# sound.net
KiCad netlist of a schematic drawn in EAGLE
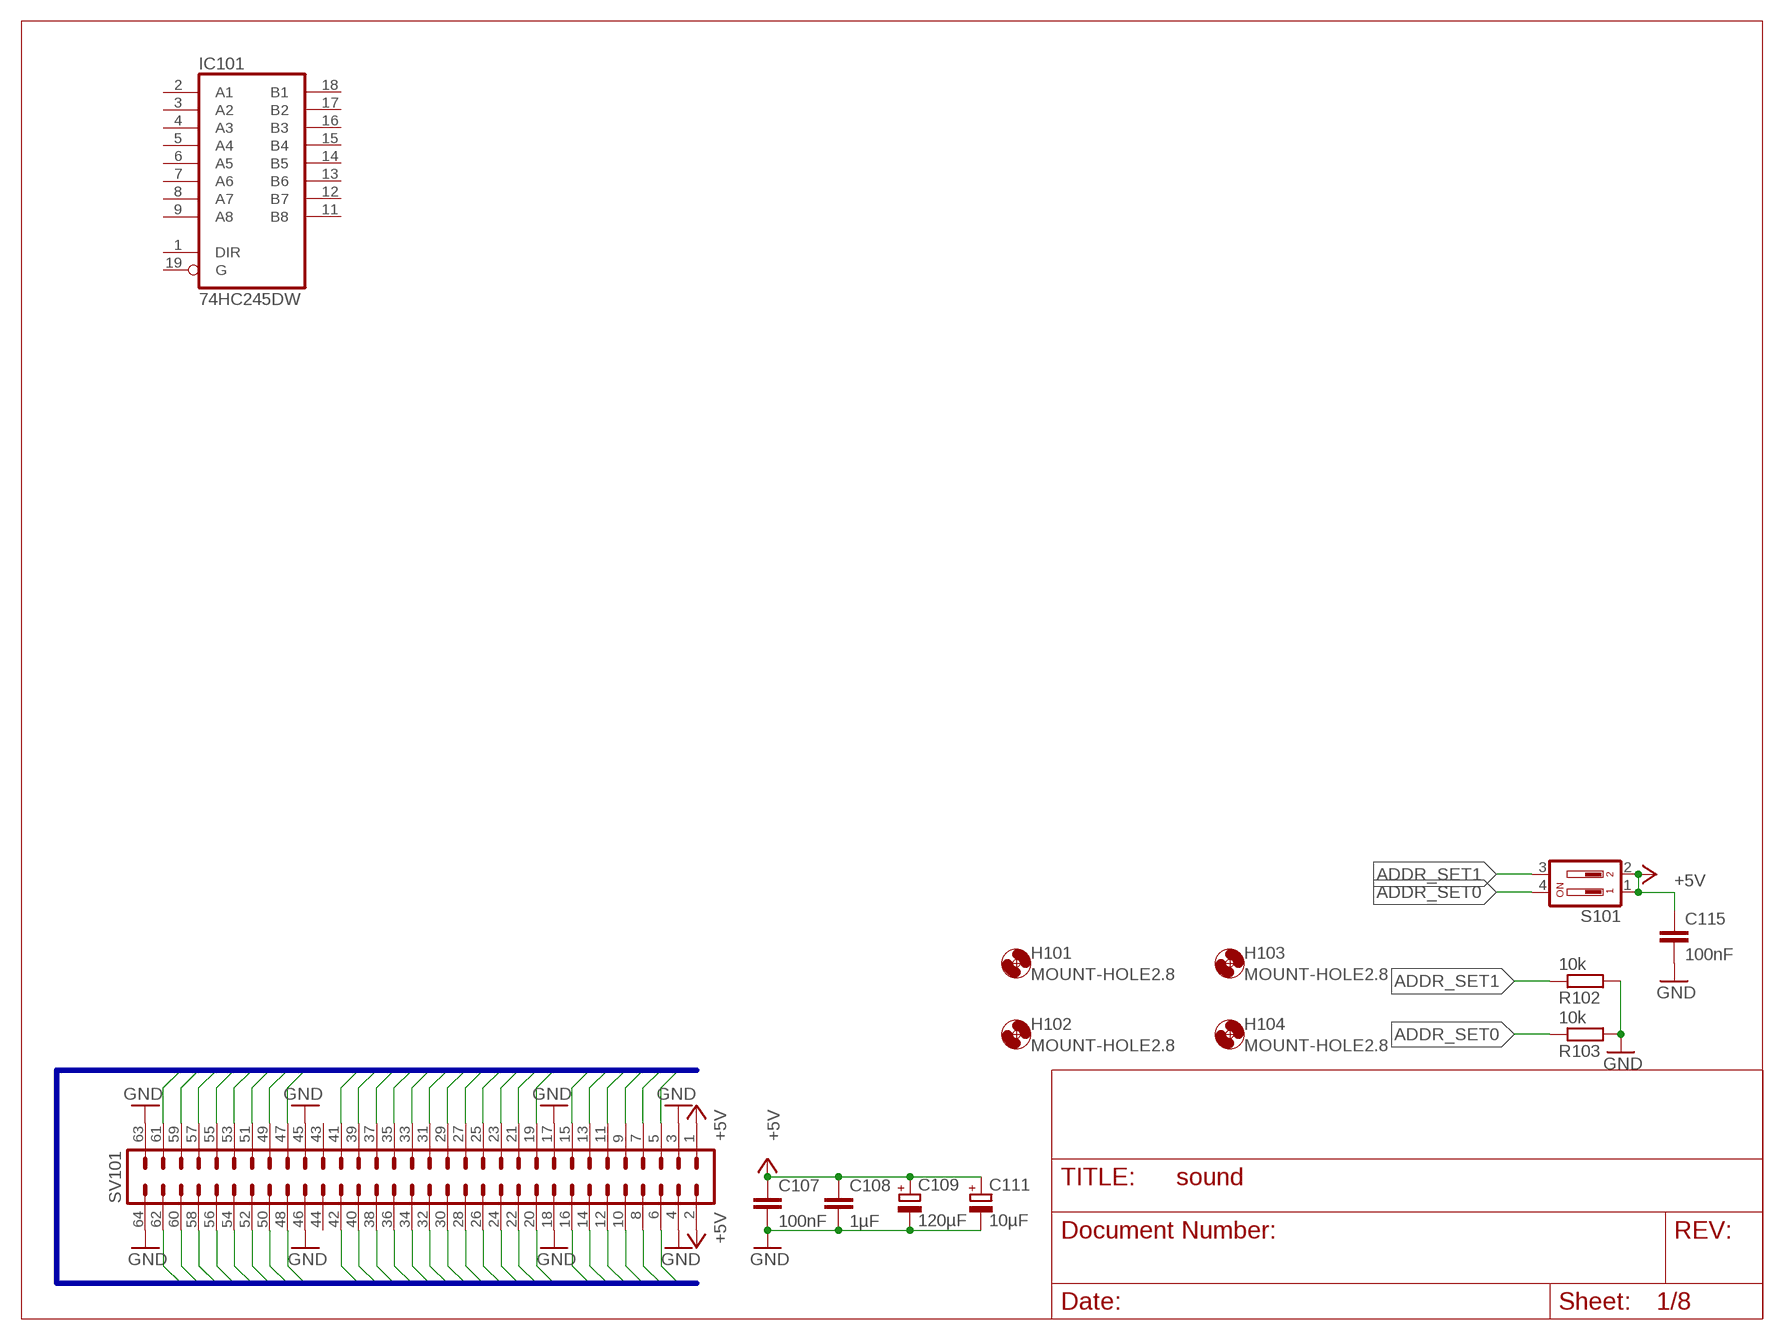
[diagram p0: schematic, sheet 1]
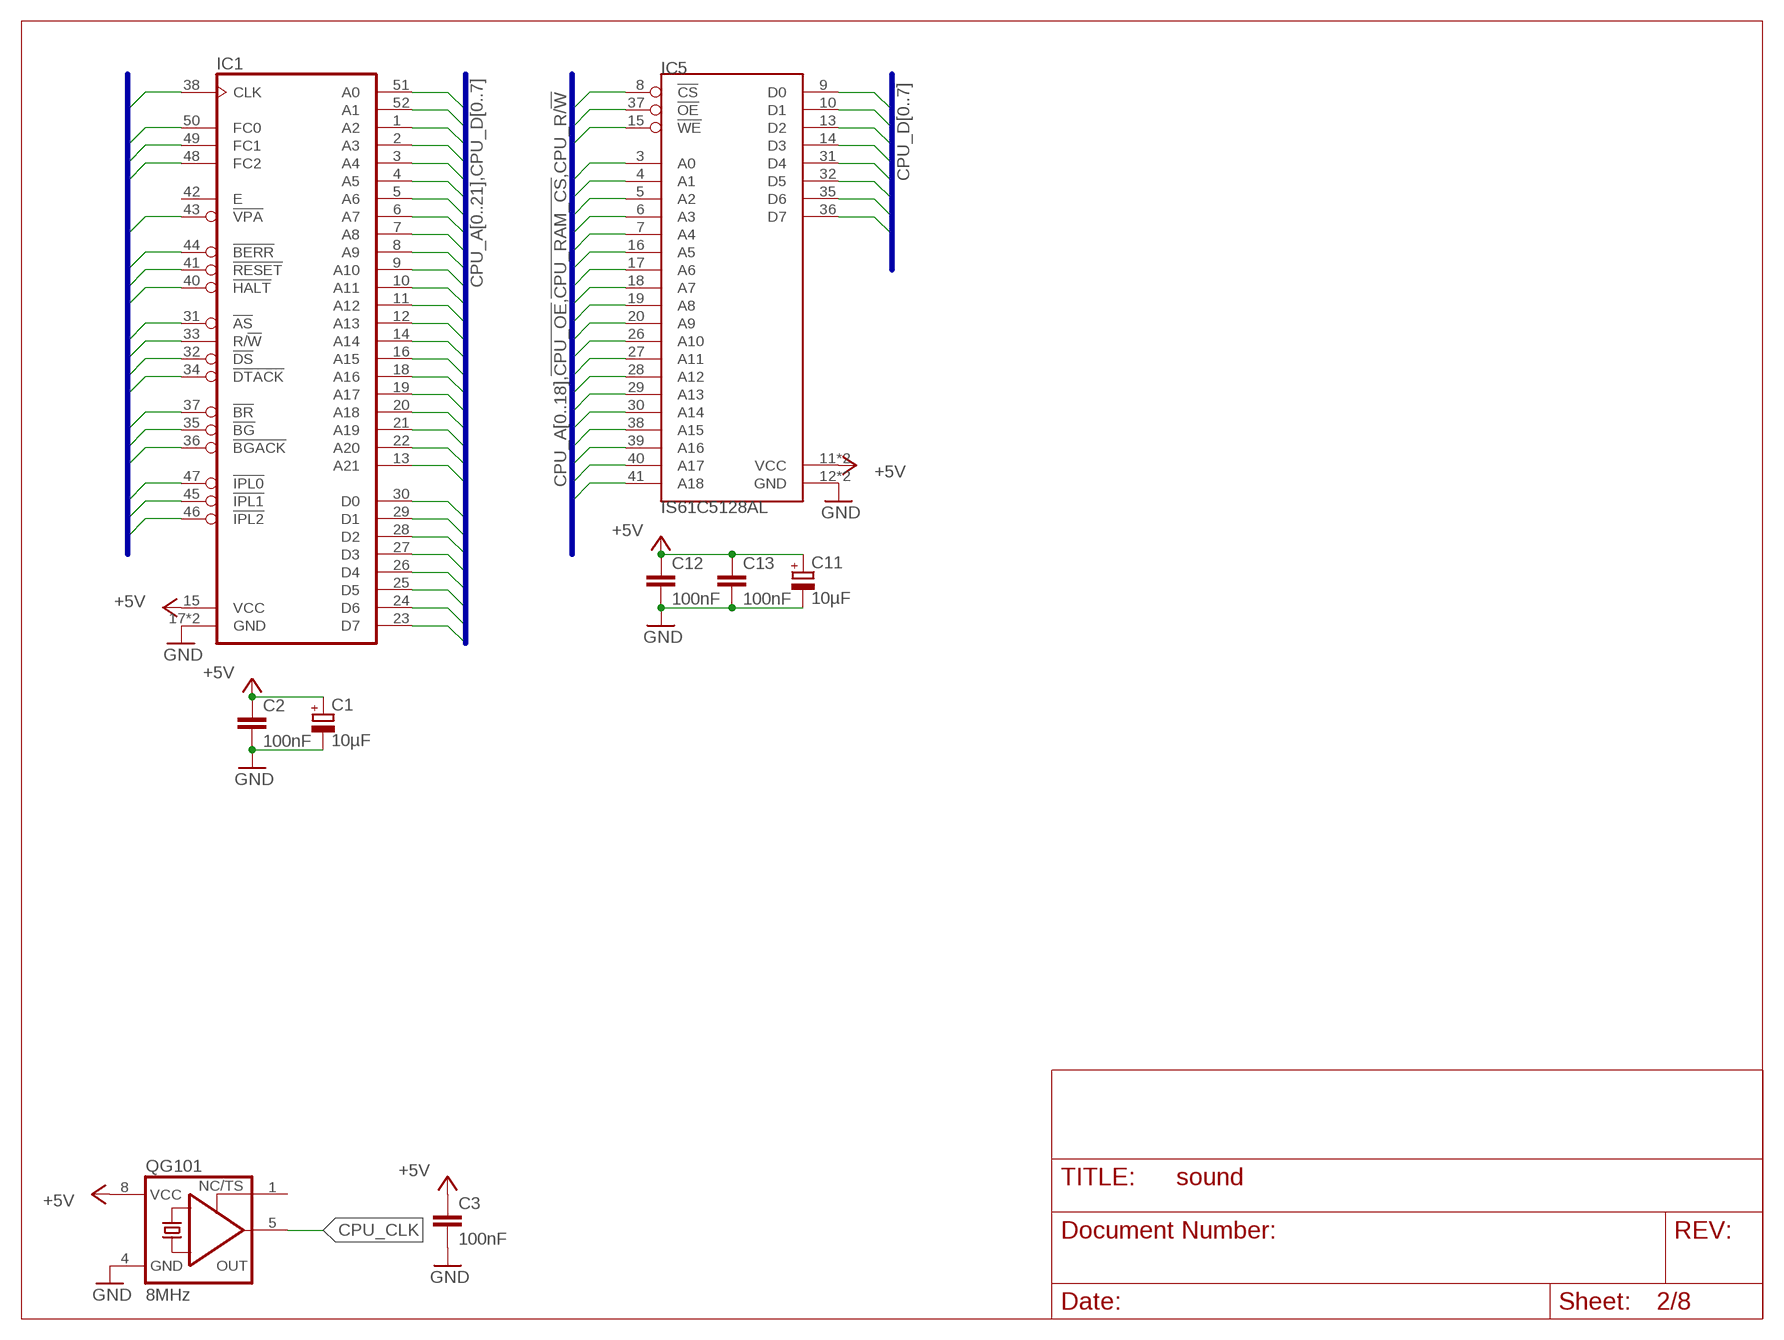
[diagram p1: schematic, sheet 2]
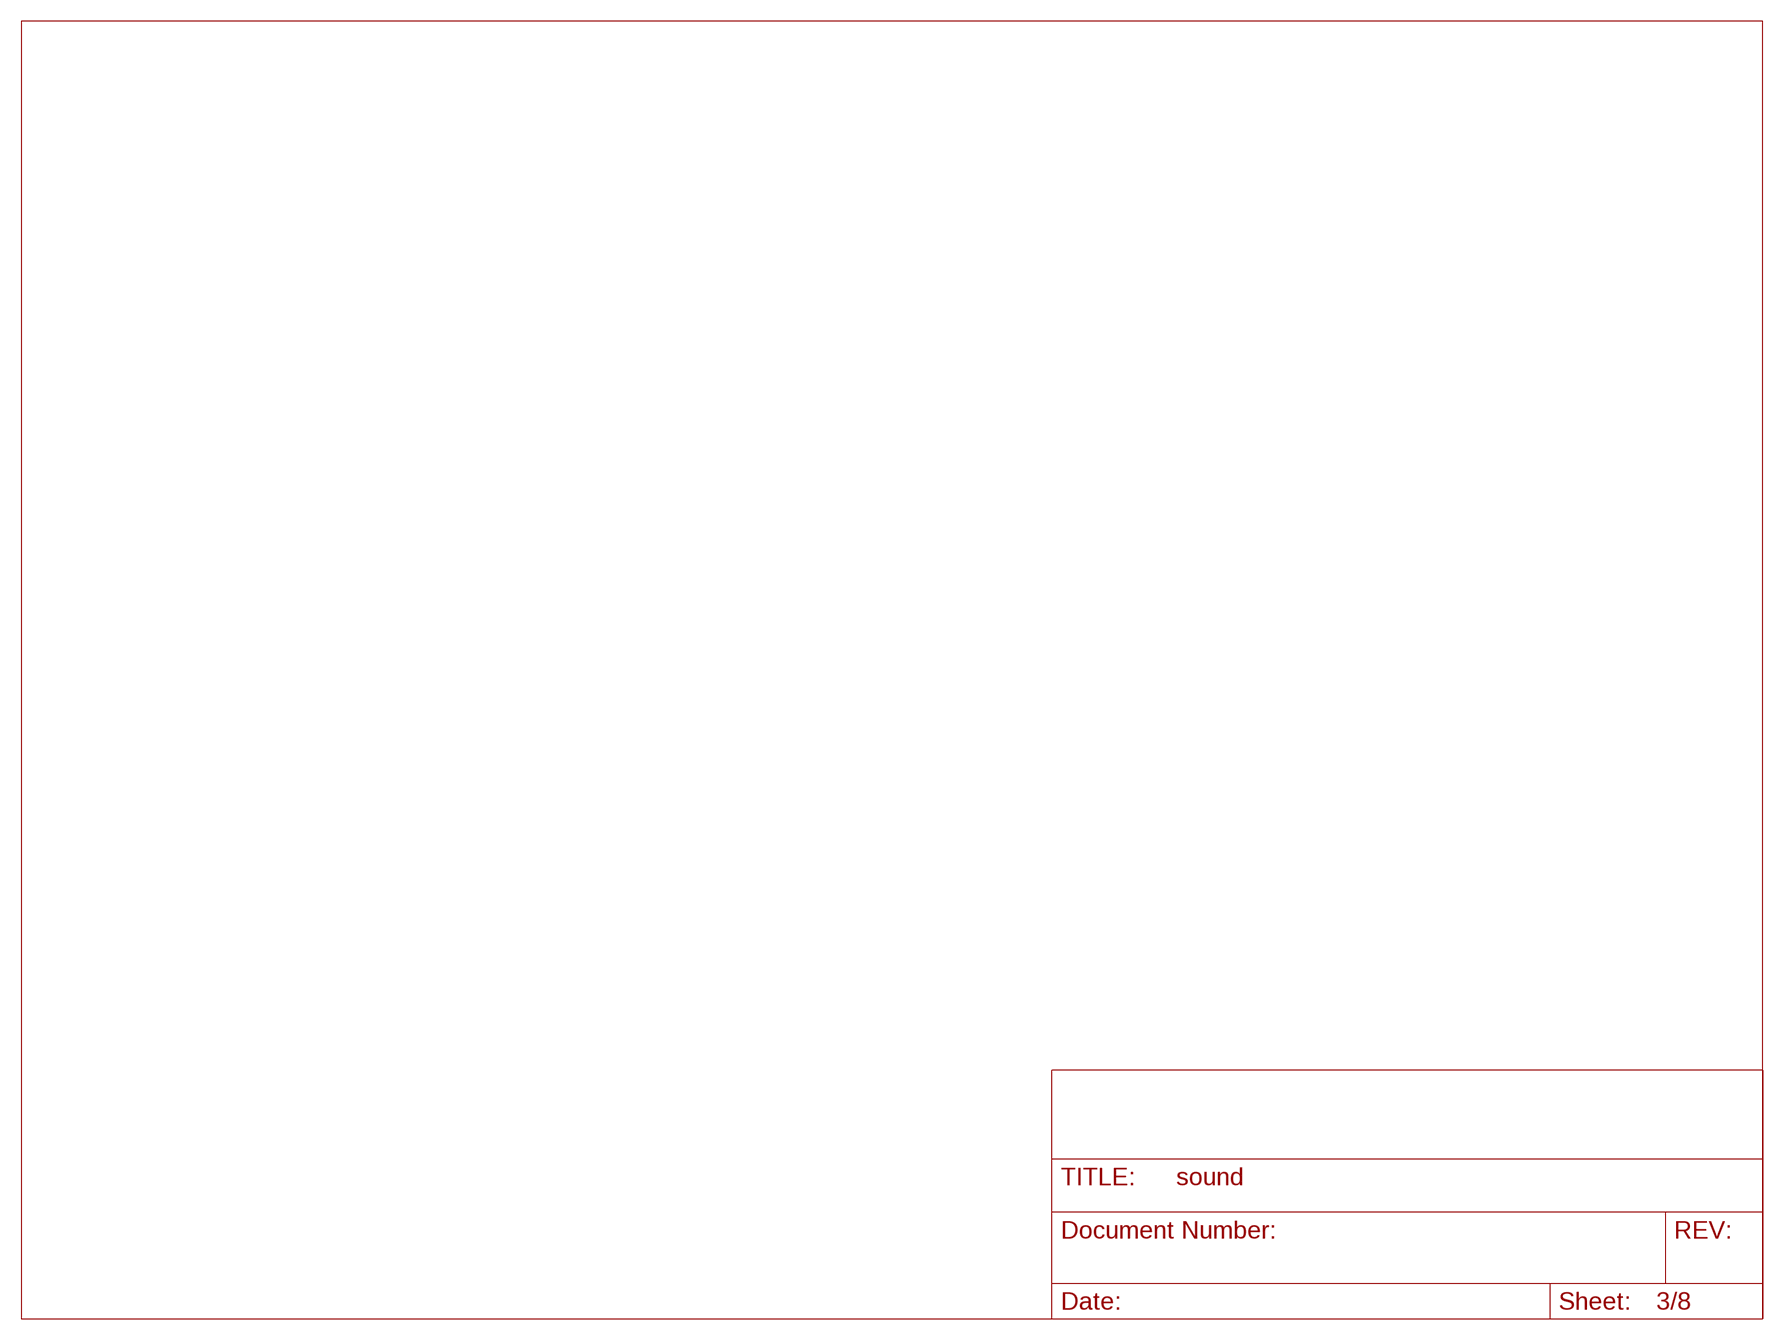
[diagram p2: schematic, sheet 3]
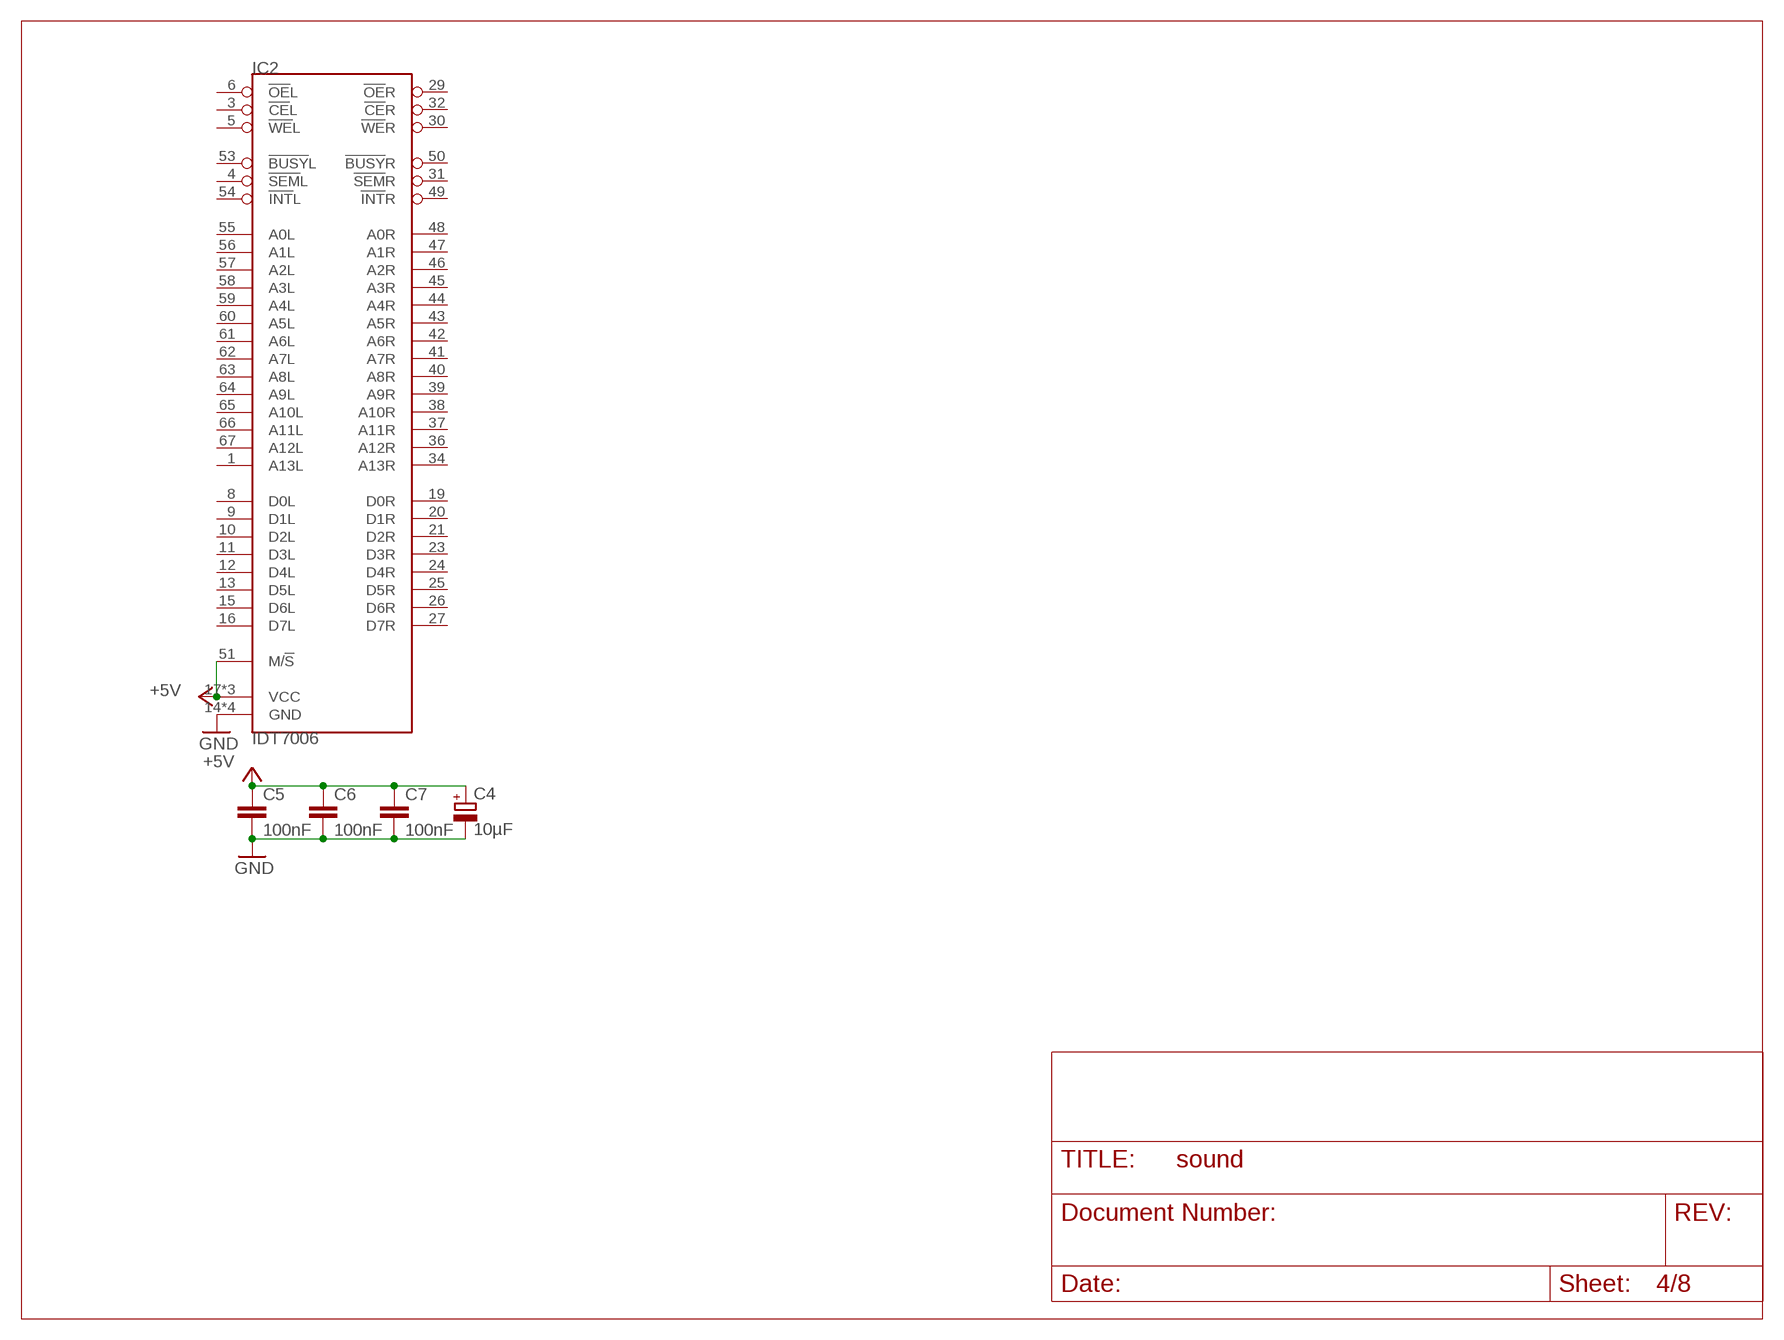
[diagram p3: schematic, sheet 4]
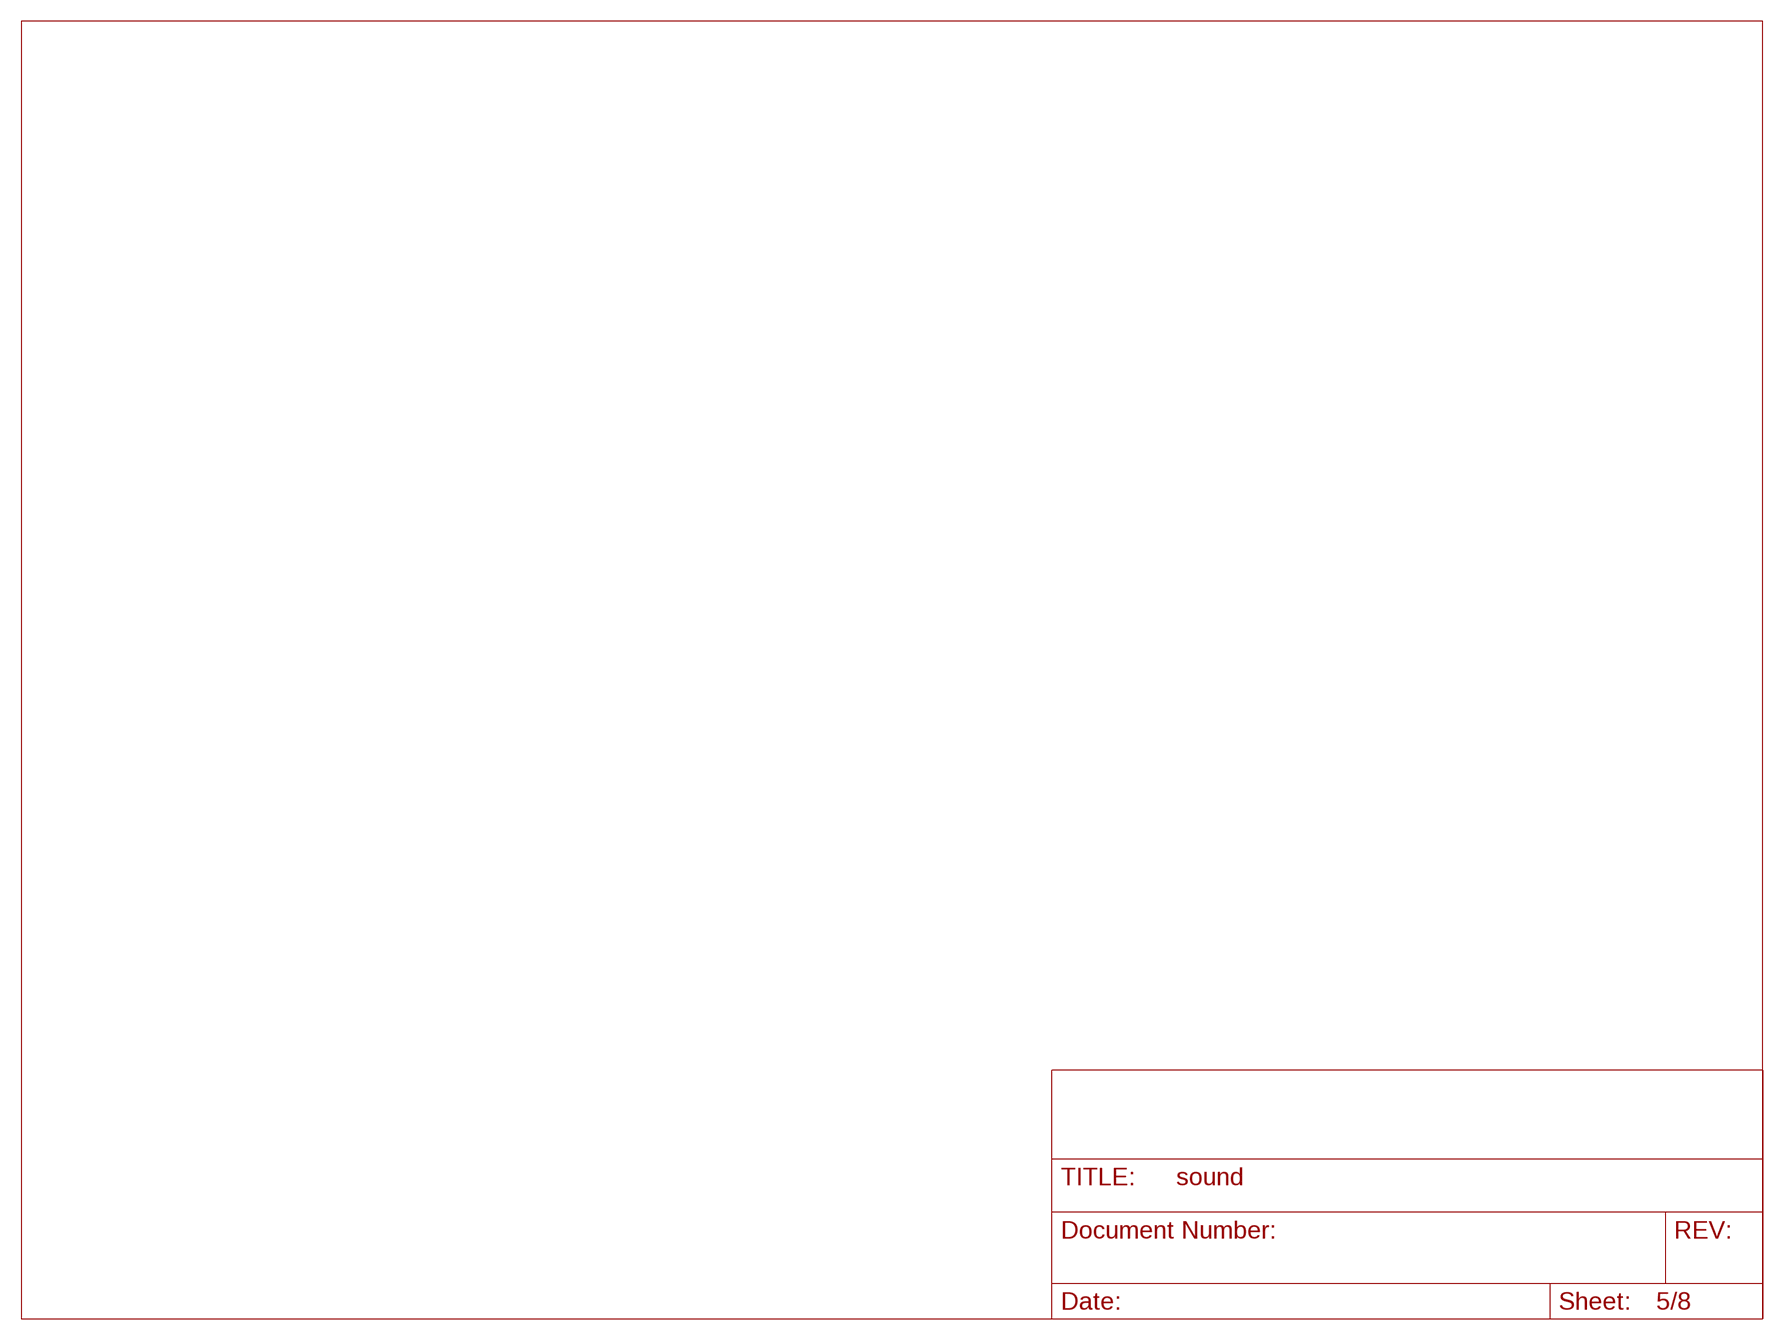
[diagram p4: schematic, sheet 5]
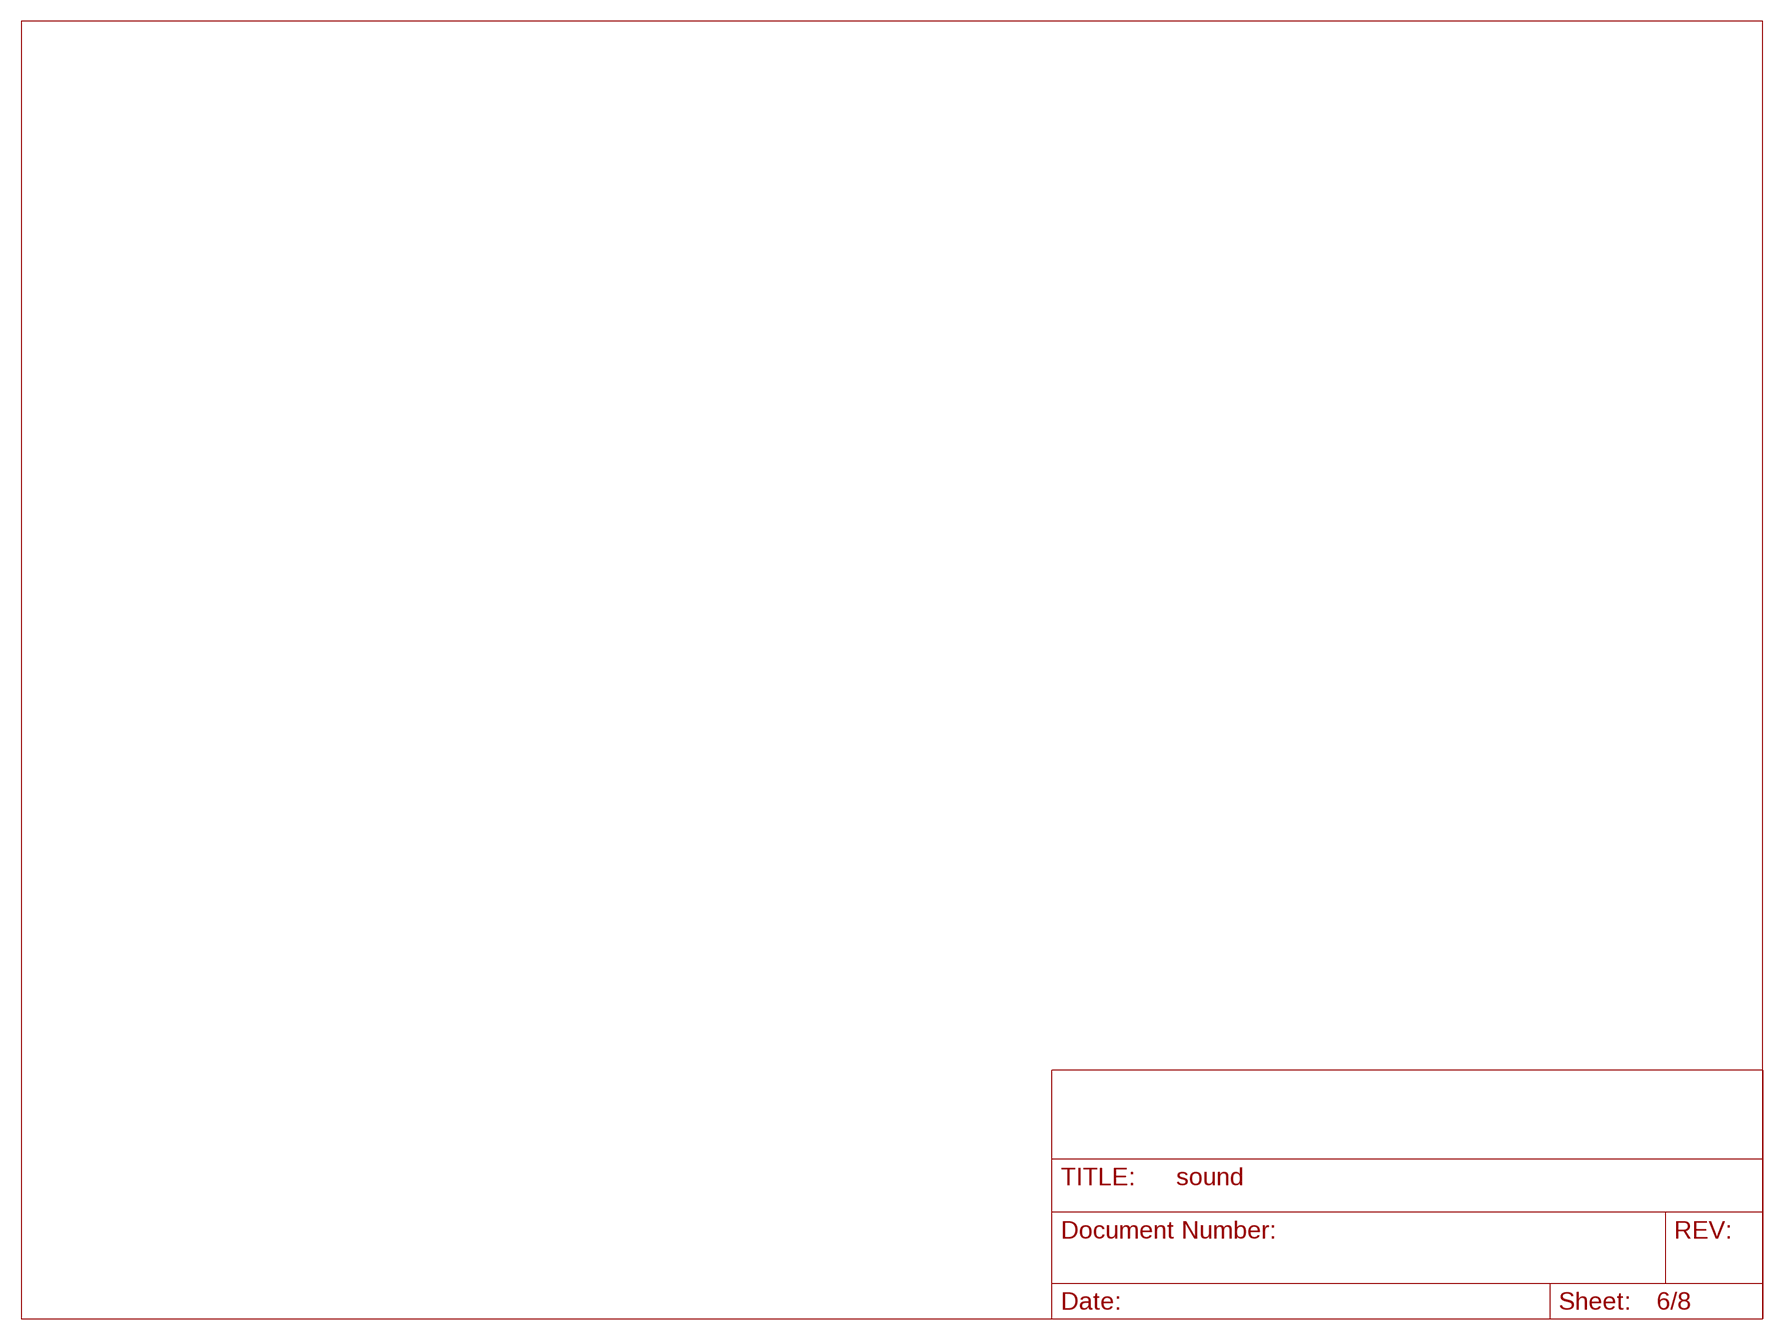
[diagram p5: schematic, sheet 6]
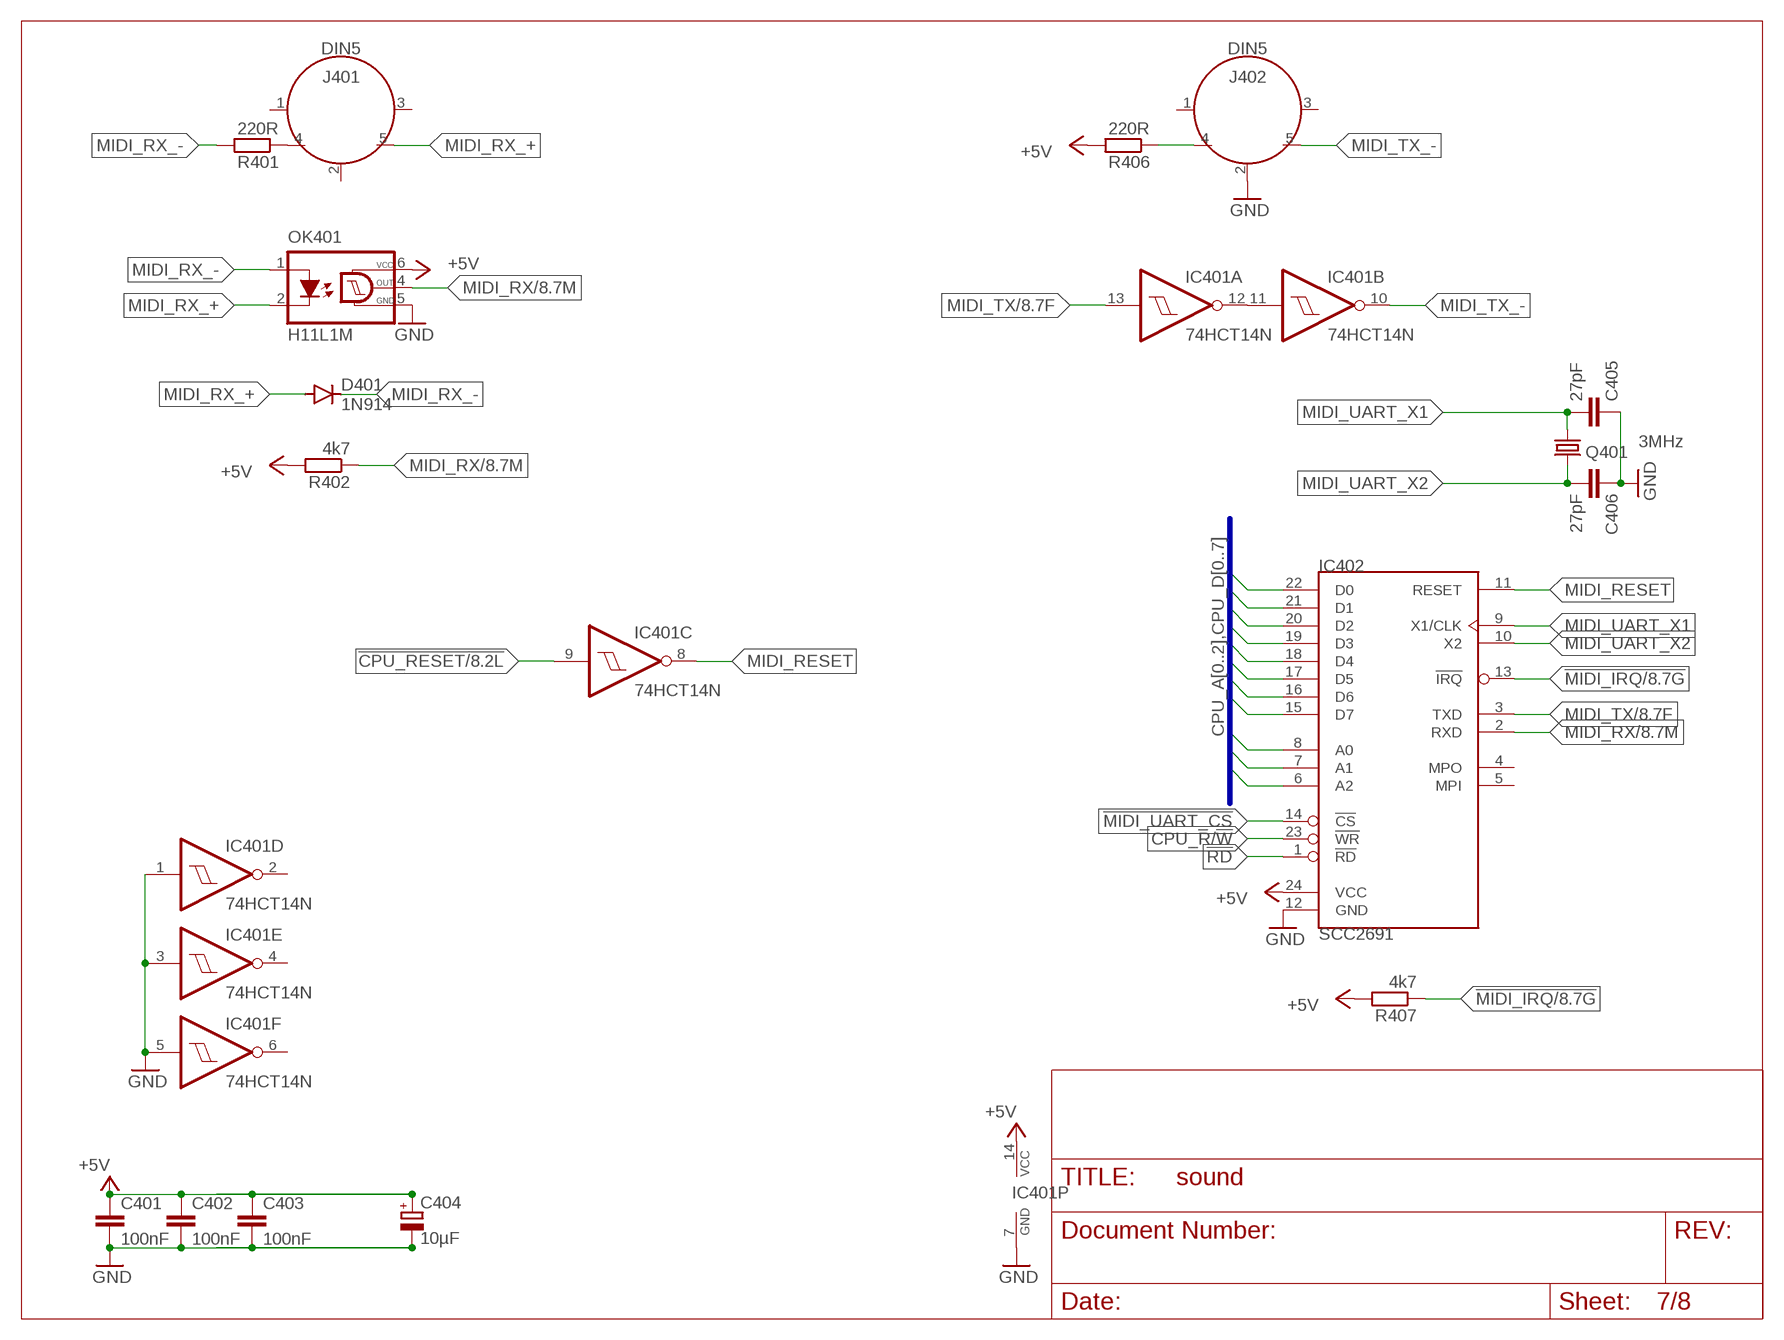
[diagram p6: schematic, sheet 7]
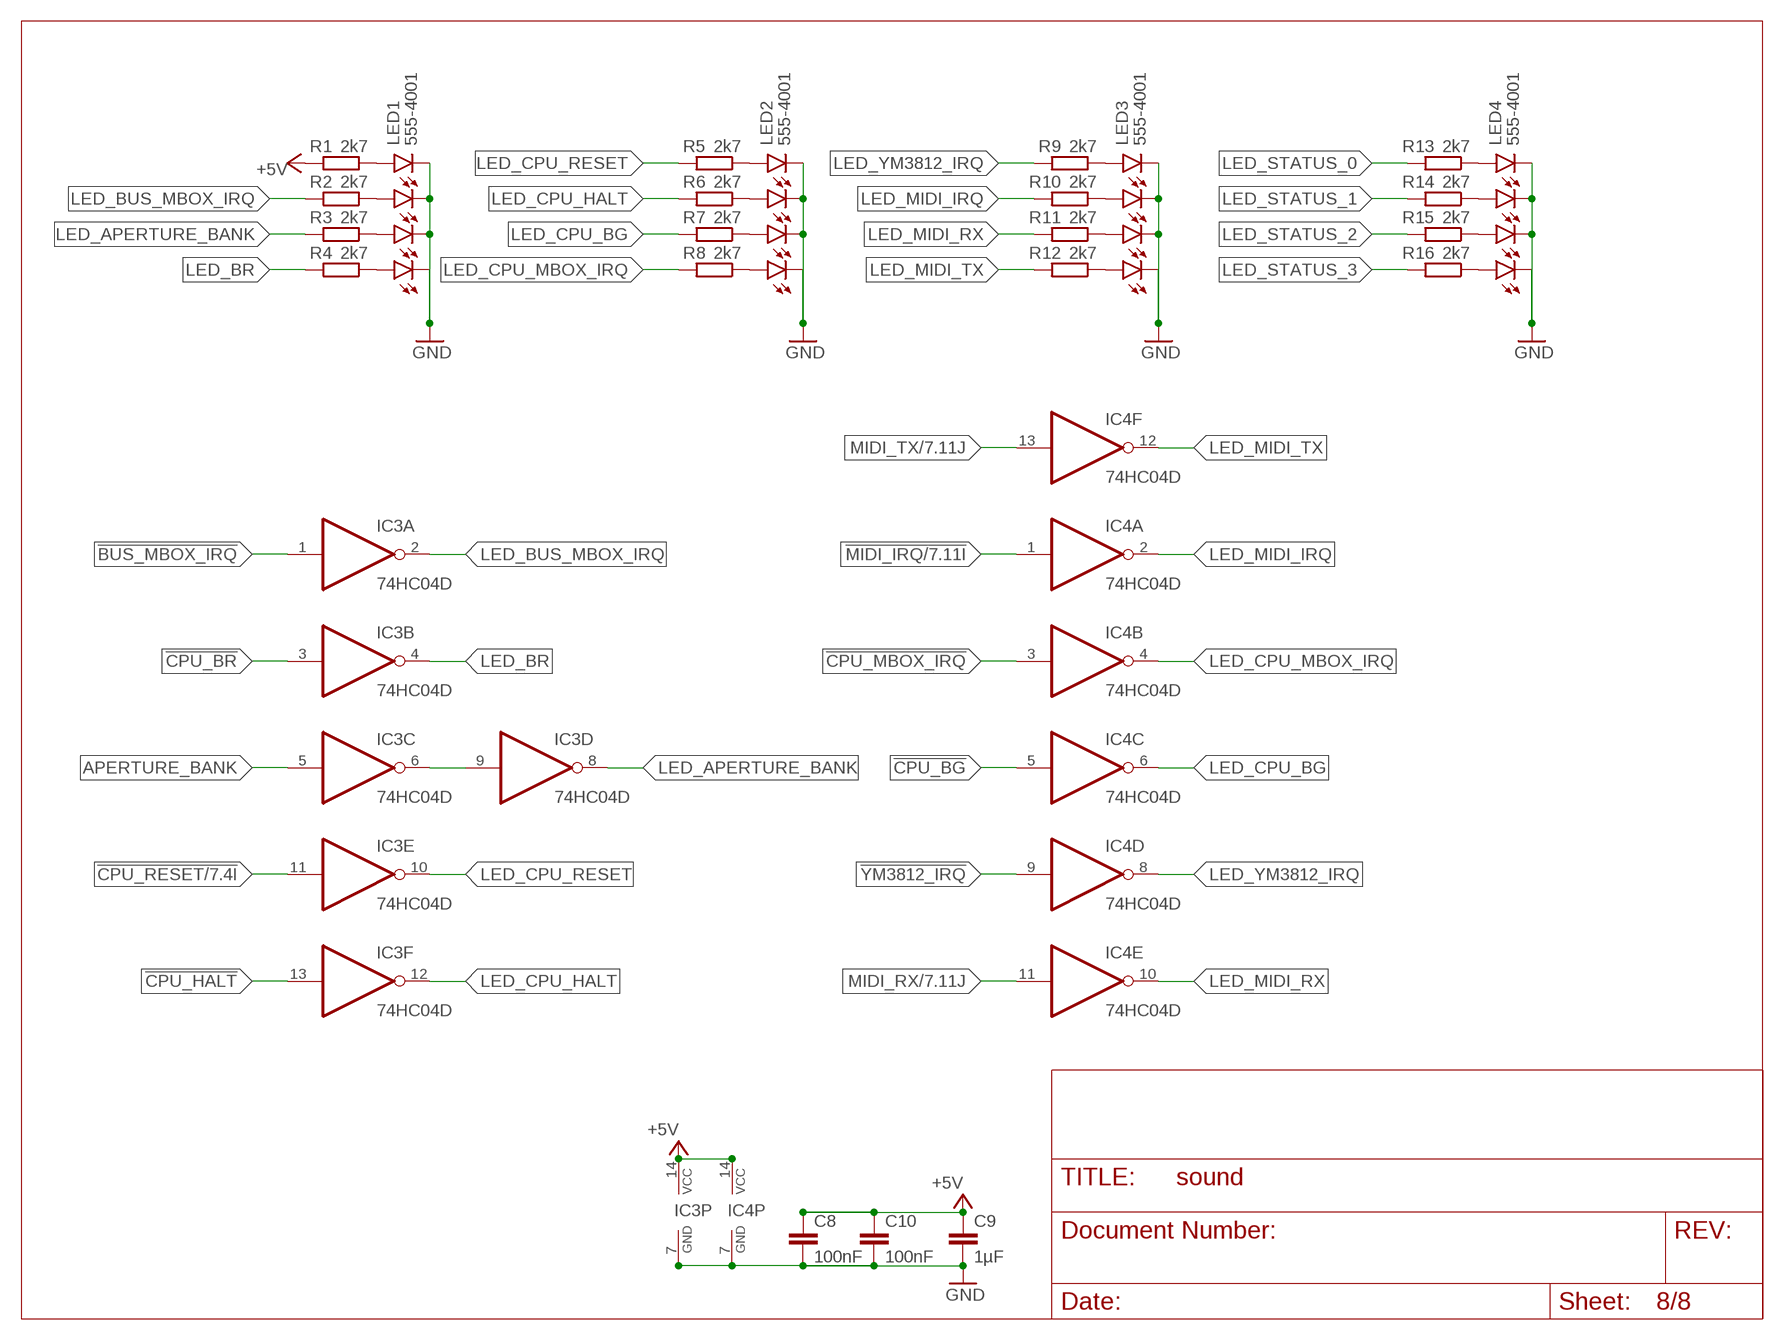
[diagram p7: schematic, sheet 8]

(export (version "E")
  (design (tool "Eeschema 10.0.6"))
  (components
    (comp (ref "C4")
      (value "10µF")
      (footprint "eagle-import:SMC_B")
      (libsource (lib "eagle-import") (part "CPOL-EUSMCB"))
    )
    (comp (ref "C5")
      (value "100nF")
      (footprint "eagle-import:C0805")
      (libsource (lib "eagle-import") (part "C-EUC0805"))
    )
    (comp (ref "C6")
      (value "100nF")
      (footprint "eagle-import:C0805")
      (libsource (lib "eagle-import") (part "C-EUC0805"))
    )
    (comp (ref "C7")
      (value "100nF")
      (footprint "eagle-import:C0805")
      (libsource (lib "eagle-import") (part "C-EUC0805"))
    )
    (comp (ref "IC2")
      (value "IDT7006")
      (footprint "eagle-import:PLCC68-S")
      (libsource (lib "eagle-import") (part "IDT7006PLCC68-S"))
    )
    (comp (ref "C107")
      (value "100nF")
      (footprint "eagle-import:C0805")
      (libsource (lib "eagle-import") (part "C-EUC0805"))
    )
    (comp (ref "C108")
      (value "1µF")
      (footprint "eagle-import:C0805")
      (libsource (lib "eagle-import") (part "C-EUC0805"))
    )
    (comp (ref "C109")
      (value "120µF")
      (footprint "eagle-import:E2,5-7")
      (libsource (lib "eagle-import") (part "CPOL-EUE2.5-7"))
    )
    (comp (ref "C111")
      (value "10µF")
      (footprint "eagle-import:SMC_B")
      (libsource (lib "eagle-import") (part "CPOL-EUSMCB"))
    )
    (comp (ref "C115")
      (value "100nF")
      (footprint "eagle-import:C0805")
      (libsource (lib "eagle-import") (part "C-EUC0805"))
    )
    (comp (ref "H101")
      (value "MOUNT-HOLE2.8")
      (footprint "eagle-import:2,8")
      (libsource (lib "eagle-import") (part "MOUNT-HOLE2.8"))
    )
    (comp (ref "H102")
      (value "MOUNT-HOLE2.8")
      (footprint "eagle-import:2,8")
      (libsource (lib "eagle-import") (part "MOUNT-HOLE2.8"))
    )
    (comp (ref "H103")
      (value "MOUNT-HOLE2.8")
      (footprint "eagle-import:2,8")
      (libsource (lib "eagle-import") (part "MOUNT-HOLE2.8"))
    )
    (comp (ref "H104")
      (value "MOUNT-HOLE2.8")
      (footprint "eagle-import:2,8")
      (libsource (lib "eagle-import") (part "MOUNT-HOLE2.8"))
    )
    (comp (ref "IC101")
      (value "74HC245DW")
      (footprint "eagle-import:SO20W")
      (libsource (lib "eagle-import") (part "74245DWHC"))
    )
    (comp (ref "R102")
      (value "10k")
      (footprint "eagle-import:R2012")
      (libsource (lib "eagle-import") (part "R-EU_R2012"))
    )
    (comp (ref "R103")
      (value "10k")
      (footprint "eagle-import:R2012")
      (libsource (lib "eagle-import") (part "R-EU_R2012"))
    )
    (comp (ref "S101")
      (value "DP02")
      (footprint "eagle-import:DP-02")
      (fields (field (name "MPN") "MCDP02"))
      (libsource (lib "eagle-import") (part "DP02"))
    )
    (comp (ref "SV101")
      (value "ML64L")
      (footprint "eagle-import:ML64L")
      (libsource (lib "eagle-import") (part "ML64L"))
    )
    (comp (ref "C401")
      (value "100nF")
      (footprint "eagle-import:C0805")
      (libsource (lib "eagle-import") (part "C-EUC0805"))
    )
    (comp (ref "C402")
      (value "100nF")
      (footprint "eagle-import:C0805")
      (libsource (lib "eagle-import") (part "C-EUC0805"))
    )
    (comp (ref "C403")
      (value "100nF")
      (footprint "eagle-import:C0805")
      (libsource (lib "eagle-import") (part "C-EUC0805"))
    )
    (comp (ref "C404")
      (value "10µF")
      (footprint "eagle-import:SMC_B")
      (libsource (lib "eagle-import") (part "CPOL-EUSMCB"))
    )
    (comp (ref "C405")
      (value "27pF")
      (footprint "eagle-import:C0805")
      (libsource (lib "eagle-import") (part "C-EUC0805"))
    )
    (comp (ref "C406")
      (value "27pF")
      (footprint "eagle-import:C0805")
      (libsource (lib "eagle-import") (part "C-EUC0805"))
    )
    (comp (ref "D401")
      (value "1N914")
      (footprint "eagle-import:DO35-10")
      (libsource (lib "eagle-import") (part "1N4148DO35-10"))
    )
    (comp (ref "IC401")
      (value "74HCT14N")
      (footprint "eagle-import:DIL14")
      (fields (field (name "MOUSER") "595-SN74HCT14N") (field (name "MOUSER_SOCKET") "575-1104731441001000"))
      (libsource (lib "eagle-import") (part "7414NHCT"))
    )
    (comp (ref "IC402")
      (value "SCC2691")
      (footprint "eagle-import:DIL24S")
      (libsource (lib "eagle-import") (part "SCC2691"))
    )
    (comp (ref "J401")
      (value "DIN5")
      (footprint "eagle-import:DIN5-RA-PTH")
      (libsource (lib "eagle-import") (part "DIN5"))
    )
    (comp (ref "J402")
      (value "DIN5")
      (footprint "eagle-import:DIN5-RA-PTH")
      (libsource (lib "eagle-import") (part "DIN5"))
    )
    (comp (ref "OK401")
      (value "H11L1M")
      (footprint "eagle-import:DIL06")
      (fields (field (name "MF") "FAIRCHILD SEMICONDUCTOR") (field (name "MPN") "H11L1-M"))
      (libsource (lib "eagle-import") (part "H11LM1"))
    )
    (comp (ref "Q401")
      (value "3MHz")
      (footprint "eagle-import:HC49_S")
      (libsource (lib "eagle-import") (part "CRYSTALHC49S"))
    )
    (comp (ref "R401")
      (value "220R")
      (footprint "eagle-import:R2012")
      (libsource (lib "eagle-import") (part "R-EU_R2012"))
    )
    (comp (ref "R402")
      (value "4k7")
      (footprint "eagle-import:R2012")
      (libsource (lib "eagle-import") (part "R-EU_R2012"))
    )
    (comp (ref "R406")
      (value "220R")
      (footprint "eagle-import:R2012")
      (libsource (lib "eagle-import") (part "R-EU_R2012"))
    )
    (comp (ref "R407")
      (value "4k7")
      (footprint "eagle-import:R2012")
      (libsource (lib "eagle-import") (part "R-EU_R2012"))
    )
    (comp (ref "C1")
      (value "10µF")
      (footprint "eagle-import:SMC_B")
      (libsource (lib "eagle-import") (part "CPOL-EUSMCB"))
    )
    (comp (ref "C2")
      (value "100nF")
      (footprint "eagle-import:C0805")
      (libsource (lib "eagle-import") (part "C-EUC0805"))
    )
    (comp (ref "C3")
      (value "100nF")
      (footprint "eagle-import:C0805")
      (libsource (lib "eagle-import") (part "C-EUC0805"))
    )
    (comp (ref "C11")
      (value "10µF")
      (footprint "eagle-import:SMC_B")
      (libsource (lib "eagle-import") (part "CPOL-EUSMCB"))
    )
    (comp (ref "C12")
      (value "100nF")
      (footprint "eagle-import:C0805")
      (libsource (lib "eagle-import") (part "C-EUC0805"))
    )
    (comp (ref "C13")
      (value "100nF")
      (footprint "eagle-import:C0805")
      (libsource (lib "eagle-import") (part "C-EUC0805"))
    )
    (comp (ref "IC1")
      (value "MC68008-PLCCPLCC52-SOCKET")
      (footprint "eagle-import:PLCC52-S")
      (libsource (lib "eagle-import") (part "MC68008-PLCCPLCC52-SOCKET"))
    )
    (comp (ref "IC5")
      (value "IS61C5128AL")
      (footprint "eagle-import:TSOP44-II")
      (libsource (lib "eagle-import") (part "IS61C5128AL"))
    )
    (comp (ref "QG101")
      (value "8MHz")
      (footprint "eagle-import:DIL08S")
      (libsource (lib "eagle-import") (part "XO-8"))
    )
    (comp (ref "C8")
      (value "100nF")
      (footprint "eagle-import:C0805")
      (libsource (lib "eagle-import") (part "C-EUC0805"))
    )
    (comp (ref "C9")
      (value "1µF")
      (footprint "eagle-import:C0805")
      (libsource (lib "eagle-import") (part "C-EUC0805"))
    )
    (comp (ref "C10")
      (value "100nF")
      (footprint "eagle-import:C0805")
      (libsource (lib "eagle-import") (part "C-EUC0805"))
    )
    (comp (ref "IC3")
      (value "74HC04D")
      (footprint "eagle-import:SO14")
      (libsource (lib "eagle-import") (part "7404DHC"))
    )
    (comp (ref "IC4")
      (value "74HC04D")
      (footprint "eagle-import:SO14")
      (libsource (lib "eagle-import") (part "7404DHC"))
    )
    (comp (ref "LED1")
      (value "555-4001")
      (footprint "eagle-import:555-4001")
      (libsource (lib "eagle-import") (part "555-4001"))
    )
    (comp (ref "LED2")
      (value "555-4001")
      (footprint "eagle-import:555-4001")
      (libsource (lib "eagle-import") (part "555-4001"))
    )
    (comp (ref "LED3")
      (value "555-4001")
      (footprint "eagle-import:555-4001")
      (libsource (lib "eagle-import") (part "555-4001"))
    )
    (comp (ref "LED4")
      (value "555-4001")
      (footprint "eagle-import:555-4001")
      (libsource (lib "eagle-import") (part "555-4001"))
    )
    (comp (ref "R1")
      (value "2k7")
      (footprint "eagle-import:R2012")
      (libsource (lib "eagle-import") (part "R-EU_R2012"))
    )
    (comp (ref "R2")
      (value "2k7")
      (footprint "eagle-import:R2012")
      (libsource (lib "eagle-import") (part "R-EU_R2012"))
    )
    (comp (ref "R3")
      (value "2k7")
      (footprint "eagle-import:R2012")
      (libsource (lib "eagle-import") (part "R-EU_R2012"))
    )
    (comp (ref "R4")
      (value "2k7")
      (footprint "eagle-import:R2012")
      (libsource (lib "eagle-import") (part "R-EU_R2012"))
    )
    (comp (ref "R5")
      (value "2k7")
      (footprint "eagle-import:R2012")
      (libsource (lib "eagle-import") (part "R-EU_R2012"))
    )
    (comp (ref "R6")
      (value "2k7")
      (footprint "eagle-import:R2012")
      (libsource (lib "eagle-import") (part "R-EU_R2012"))
    )
    (comp (ref "R7")
      (value "2k7")
      (footprint "eagle-import:R2012")
      (libsource (lib "eagle-import") (part "R-EU_R2012"))
    )
    (comp (ref "R8")
      (value "2k7")
      (footprint "eagle-import:R2012")
      (libsource (lib "eagle-import") (part "R-EU_R2012"))
    )
    (comp (ref "R9")
      (value "2k7")
      (footprint "eagle-import:R2012")
      (libsource (lib "eagle-import") (part "R-EU_R2012"))
    )
    (comp (ref "R10")
      (value "2k7")
      (footprint "eagle-import:R2012")
      (libsource (lib "eagle-import") (part "R-EU_R2012"))
    )
    (comp (ref "R11")
      (value "2k7")
      (footprint "eagle-import:R2012")
      (libsource (lib "eagle-import") (part "R-EU_R2012"))
    )
    (comp (ref "R12")
      (value "2k7")
      (footprint "eagle-import:R2012")
      (libsource (lib "eagle-import") (part "R-EU_R2012"))
    )
    (comp (ref "R13")
      (value "2k7")
      (footprint "eagle-import:R2012")
      (libsource (lib "eagle-import") (part "R-EU_R2012"))
    )
    (comp (ref "R14")
      (value "2k7")
      (footprint "eagle-import:R2012")
      (libsource (lib "eagle-import") (part "R-EU_R2012"))
    )
    (comp (ref "R15")
      (value "2k7")
      (footprint "eagle-import:R2012")
      (libsource (lib "eagle-import") (part "R-EU_R2012"))
    )
    (comp (ref "R16")
      (value "2k7")
      (footprint "eagle-import:R2012")
      (libsource (lib "eagle-import") (part "R-EU_R2012"))
    )
  )
  (nets
    (net (code "3") (name "+5V") (class "Default")
      (node (ref "C1") (pin "+") (pinfunction "+_+") (pintype "passive"))
      (node (ref "C10") (pin "1") (pinfunction "1_1") (pintype "passive"))
      (node (ref "C107") (pin "1") (pinfunction "1_1") (pintype "passive"))
      (node (ref "C108") (pin "1") (pinfunction "1_1") (pintype "passive"))
      (node (ref "C109") (pin "+") (pinfunction "+_+") (pintype "passive"))
      (node (ref "C11") (pin "+") (pinfunction "+_+") (pintype "passive"))
      (node (ref "C111") (pin "+") (pinfunction "+_+") (pintype "passive"))
      (node (ref "C115") (pin "1") (pinfunction "1_1") (pintype "passive"))
      (node (ref "C12") (pin "1") (pinfunction "1_1") (pintype "passive"))
      (node (ref "C13") (pin "1") (pinfunction "1_1") (pintype "passive"))
      (node (ref "C2") (pin "1") (pinfunction "1_1") (pintype "passive"))
      (node (ref "C3") (pin "1") (pinfunction "1_1") (pintype "passive"))
      (node (ref "C4") (pin "+") (pinfunction "+_+") (pintype "passive"))
      (node (ref "C401") (pin "1") (pinfunction "1_1") (pintype "passive"))
      (node (ref "C402") (pin "1") (pinfunction "1_1") (pintype "passive"))
      (node (ref "C403") (pin "1") (pinfunction "1_1") (pintype "passive"))
      (node (ref "C404") (pin "+") (pinfunction "+_+") (pintype "passive"))
      (node (ref "C5") (pin "1") (pinfunction "1_1") (pintype "passive"))
      (node (ref "C6") (pin "1") (pinfunction "1_1") (pintype "passive"))
      (node (ref "C7") (pin "1") (pinfunction "1_1") (pintype "passive"))
      (node (ref "C8") (pin "1") (pinfunction "1_1") (pintype "passive"))
      (node (ref "C9") (pin "1") (pinfunction "1_1") (pintype "passive"))
      (node (ref "IC1") (pin "15") (pinfunction "VCC_15") (pintype "power_in"))
      (node (ref "IC2") (pin "17") (pinfunction "VCC_17") (pintype "power_in"))
      (node (ref "IC2") (pin "22") (pinfunction "VCC_22") (pintype "power_in"))
      (node (ref "IC2") (pin "51") (pinfunction "M/~{S}_51") (pintype "input"))
      (node (ref "IC2") (pin "68") (pinfunction "VCC_68") (pintype "power_in"))
      (node (ref "IC3") (pin "14") (pinfunction "VCC_14") (pintype "power_in"))
      (node (ref "IC4") (pin "14") (pinfunction "VCC_14") (pintype "power_in"))
      (node (ref "IC401") (pin "14") (pinfunction "VCC_14") (pintype "power_in"))
      (node (ref "IC402") (pin "24") (pinfunction "VCC_24") (pintype "power_in"))
      (node (ref "IC5") (pin "11") (pinfunction "VCC_11") (pintype "power_in"))
      (node (ref "IC5") (pin "33") (pinfunction "VCC_33") (pintype "power_in"))
      (node (ref "OK401") (pin "6") (pinfunction "VCC_6") (pintype "power_in"))
      (node (ref "QG101") (pin "8") (pinfunction "VCC_8") (pintype "power_in"))
      (node (ref "R1") (pin "2") (pinfunction "2_2") (pintype "passive"))
      (node (ref "R402") (pin "2") (pinfunction "2_2") (pintype "passive"))
      (node (ref "R406") (pin "2") (pinfunction "2_2") (pintype "passive"))
      (node (ref "R407") (pin "2") (pinfunction "2_2") (pintype "passive"))
      (node (ref "S101") (pin "1") (pinfunction "1_1") (pintype "passive"))
      (node (ref "S101") (pin "2") (pinfunction "2_2") (pintype "passive"))
      (node (ref "SV101") (pin "1") (pinfunction "1_1") (pintype "passive"))
      (node (ref "SV101") (pin "2") (pinfunction "2_2") (pintype "passive"))
    )
    (net (code "8") (name "ADDR_SET0") (class "Default")
      (node (ref "R103") (pin "1") (pinfunction "1_1") (pintype "passive"))
      (node (ref "S101") (pin "4") (pinfunction "4_4") (pintype "passive"))
    )
    (net (code "9") (name "ADDR_SET1") (class "Default")
      (node (ref "R102") (pin "1") (pinfunction "1_1") (pintype "passive"))
      (node (ref "S101") (pin "3") (pinfunction "3_3") (pintype "passive"))
    )
    (net (code "10") (name "APERTURE_BANK") (class "Default")
      (node (ref "IC3") (pin "5") (pinfunction "I_5") (pintype "input"))
    )
    (net (code "11") (name "CPU_A0") (class "Default")
      (node (ref "IC1") (pin "51") (pinfunction "A0_51") (pintype "output"))
      (node (ref "IC402") (pin "8") (pinfunction "A0_8") (pintype "input"))
      (node (ref "IC5") (pin "3") (pinfunction "A0_3") (pintype "input"))
    )
    (net (code "12") (name "CPU_A1") (class "Default")
      (node (ref "IC1") (pin "52") (pinfunction "A1_52") (pintype "output"))
      (node (ref "IC402") (pin "7") (pinfunction "A1_7") (pintype "input"))
      (node (ref "IC5") (pin "4") (pinfunction "A1_4") (pintype "input"))
    )
    (net (code "13") (name "CPU_A2") (class "Default")
      (node (ref "IC1") (pin "1") (pinfunction "A2_1") (pintype "output"))
      (node (ref "IC402") (pin "6") (pinfunction "A2_6") (pintype "input"))
      (node (ref "IC5") (pin "5") (pinfunction "A2_5") (pintype "input"))
    )
    (net (code "14") (name "CPU_A3") (class "Default")
      (node (ref "IC1") (pin "2") (pinfunction "A3_2") (pintype "output"))
      (node (ref "IC5") (pin "6") (pinfunction "A3_6") (pintype "input"))
    )
    (net (code "15") (name "CPU_A4") (class "Default")
      (node (ref "IC1") (pin "3") (pinfunction "A4_3") (pintype "output"))
      (node (ref "IC5") (pin "7") (pinfunction "A4_7") (pintype "input"))
    )
    (net (code "16") (name "CPU_A5") (class "Default")
      (node (ref "IC1") (pin "4") (pinfunction "A5_4") (pintype "output"))
      (node (ref "IC5") (pin "16") (pinfunction "A5_16") (pintype "input"))
    )
    (net (code "17") (name "CPU_A6") (class "Default")
      (node (ref "IC1") (pin "5") (pinfunction "A6_5") (pintype "output"))
      (node (ref "IC5") (pin "17") (pinfunction "A6_17") (pintype "input"))
    )
    (net (code "18") (name "CPU_A7") (class "Default")
      (node (ref "IC1") (pin "6") (pinfunction "A7_6") (pintype "output"))
      (node (ref "IC5") (pin "18") (pinfunction "A7_18") (pintype "input"))
    )
    (net (code "19") (name "CPU_A8") (class "Default")
      (node (ref "IC1") (pin "7") (pinfunction "A8_7") (pintype "output"))
      (node (ref "IC5") (pin "19") (pinfunction "A8_19") (pintype "input"))
    )
    (net (code "20") (name "CPU_A9") (class "Default")
      (node (ref "IC1") (pin "8") (pinfunction "A9_8") (pintype "output"))
      (node (ref "IC5") (pin "20") (pinfunction "A9_20") (pintype "input"))
    )
    (net (code "21") (name "CPU_A10") (class "Default")
      (node (ref "IC1") (pin "9") (pinfunction "A10_9") (pintype "output"))
      (node (ref "IC5") (pin "26") (pinfunction "A10_26") (pintype "input"))
    )
    (net (code "22") (name "CPU_A11") (class "Default")
      (node (ref "IC1") (pin "10") (pinfunction "A11_10") (pintype "output"))
      (node (ref "IC5") (pin "27") (pinfunction "A11_27") (pintype "input"))
    )
    (net (code "23") (name "CPU_A12") (class "Default")
      (node (ref "IC1") (pin "11") (pinfunction "A12_11") (pintype "output"))
      (node (ref "IC5") (pin "28") (pinfunction "A12_28") (pintype "input"))
    )
    (net (code "24") (name "CPU_A13") (class "Default")
      (node (ref "IC1") (pin "12") (pinfunction "A13_12") (pintype "output"))
      (node (ref "IC5") (pin "29") (pinfunction "A13_29") (pintype "input"))
    )
    (net (code "25") (name "CPU_A14") (class "Default")
      (node (ref "IC1") (pin "14") (pinfunction "A14_14") (pintype "output"))
      (node (ref "IC5") (pin "30") (pinfunction "A14_30") (pintype "input"))
    )
    (net (code "26") (name "CPU_A15") (class "Default")
      (node (ref "IC1") (pin "16") (pinfunction "A15_16") (pintype "output"))
      (node (ref "IC5") (pin "38") (pinfunction "A15_38") (pintype "input"))
    )
    (net (code "27") (name "CPU_A16") (class "Default")
      (node (ref "IC1") (pin "18") (pinfunction "A16_18") (pintype "output"))
      (node (ref "IC5") (pin "39") (pinfunction "A16_39") (pintype "input"))
    )
    (net (code "28") (name "CPU_A17") (class "Default")
      (node (ref "IC1") (pin "19") (pinfunction "A17_19") (pintype "output"))
      (node (ref "IC5") (pin "40") (pinfunction "A17_40") (pintype "input"))
    )
    (net (code "29") (name "CPU_A18") (class "Default")
      (node (ref "IC1") (pin "20") (pinfunction "A18_20") (pintype "output"))
      (node (ref "IC5") (pin "41") (pinfunction "A18_41") (pintype "input"))
    )
    (net (code "30") (name "CPU_CLK") (class "Default")
      (node (ref "IC1") (pin "38") (pinfunction "CLK_38") (pintype "input"))
      (node (ref "QG101") (pin "5") (pinfunction "OUT_5") (pintype "output"))
    )
    (net (code "31") (name "CPU_D0") (class "Default")
      (node (ref "IC1") (pin "30") (pinfunction "D0_30") (pintype "bidirectional"))
      (node (ref "IC402") (pin "22") (pinfunction "D0_22") (pintype "bidirectional"))
      (node (ref "IC5") (pin "9") (pinfunction "D0_9") (pintype "bidirectional"))
    )
    (net (code "32") (name "CPU_D1") (class "Default")
      (node (ref "IC1") (pin "29") (pinfunction "D1_29") (pintype "bidirectional"))
      (node (ref "IC402") (pin "21") (pinfunction "D1_21") (pintype "bidirectional"))
      (node (ref "IC5") (pin "10") (pinfunction "D1_10") (pintype "bidirectional"))
    )
    (net (code "33") (name "CPU_D2") (class "Default")
      (node (ref "IC1") (pin "28") (pinfunction "D2_28") (pintype "bidirectional"))
      (node (ref "IC402") (pin "20") (pinfunction "D2_20") (pintype "bidirectional"))
      (node (ref "IC5") (pin "13") (pinfunction "D2_13") (pintype "bidirectional"))
    )
    (net (code "34") (name "CPU_D3") (class "Default")
      (node (ref "IC1") (pin "27") (pinfunction "D3_27") (pintype "bidirectional"))
      (node (ref "IC402") (pin "19") (pinfunction "D3_19") (pintype "bidirectional"))
      (node (ref "IC5") (pin "14") (pinfunction "D3_14") (pintype "bidirectional"))
    )
    (net (code "35") (name "CPU_D4") (class "Default")
      (node (ref "IC1") (pin "26") (pinfunction "D4_26") (pintype "bidirectional"))
      (node (ref "IC402") (pin "18") (pinfunction "D4_18") (pintype "bidirectional"))
      (node (ref "IC5") (pin "31") (pinfunction "D4_31") (pintype "bidirectional"))
    )
    (net (code "36") (name "CPU_D5") (class "Default")
      (node (ref "IC1") (pin "25") (pinfunction "D5_25") (pintype "bidirectional"))
      (node (ref "IC402") (pin "17") (pinfunction "D5_17") (pintype "bidirectional"))
      (node (ref "IC5") (pin "32") (pinfunction "D5_32") (pintype "bidirectional"))
    )
    (net (code "37") (name "CPU_D6") (class "Default")
      (node (ref "IC1") (pin "24") (pinfunction "D6_24") (pintype "bidirectional"))
      (node (ref "IC402") (pin "16") (pinfunction "D6_16") (pintype "bidirectional"))
      (node (ref "IC5") (pin "35") (pinfunction "D6_35") (pintype "bidirectional"))
    )
    (net (code "38") (name "CPU_D7") (class "Default")
      (node (ref "IC1") (pin "23") (pinfunction "D7_23") (pintype "bidirectional"))
      (node (ref "IC402") (pin "15") (pinfunction "D7_15") (pintype "bidirectional"))
      (node (ref "IC5") (pin "36") (pinfunction "D7_36") (pintype "bidirectional"))
    )
    (net (code "39") (name "CPU_R{slash}~{W}") (class "Default")
      (node (ref "IC1") (pin "33") (pinfunction "R/~{W}_33") (pintype "output"))
      (node (ref "IC402") (pin "23") (pinfunction "~{WR}_23") (pintype "input"))
      (node (ref "IC5") (pin "15") (pinfunction "~{WE}_15") (pintype "input"))
    )
    (net (code "40") (name "GND") (class "Default")
      (node (ref "C1") (pin "-") (pinfunction "-_-") (pintype "passive"))
      (node (ref "C10") (pin "2") (pinfunction "2_2") (pintype "passive"))
      (node (ref "C107") (pin "2") (pinfunction "2_2") (pintype "passive"))
      (node (ref "C108") (pin "2") (pinfunction "2_2") (pintype "passive"))
      (node (ref "C109") (pin "-") (pinfunction "-_-") (pintype "passive"))
      (node (ref "C11") (pin "-") (pinfunction "-_-") (pintype "passive"))
      (node (ref "C111") (pin "-") (pinfunction "-_-") (pintype "passive"))
      (node (ref "C115") (pin "2") (pinfunction "2_2") (pintype "passive"))
      (node (ref "C12") (pin "2") (pinfunction "2_2") (pintype "passive"))
      (node (ref "C13") (pin "2") (pinfunction "2_2") (pintype "passive"))
      (node (ref "C2") (pin "2") (pinfunction "2_2") (pintype "passive"))
      (node (ref "C3") (pin "2") (pinfunction "2_2") (pintype "passive"))
      (node (ref "C4") (pin "-") (pinfunction "-_-") (pintype "passive"))
      (node (ref "C401") (pin "2") (pinfunction "2_2") (pintype "passive"))
      (node (ref "C402") (pin "2") (pinfunction "2_2") (pintype "passive"))
      (node (ref "C403") (pin "2") (pinfunction "2_2") (pintype "passive"))
      (node (ref "C404") (pin "-") (pinfunction "-_-") (pintype "passive"))
      (node (ref "C405") (pin "1") (pinfunction "1_1") (pintype "passive"))
      (node (ref "C406") (pin "1") (pinfunction "1_1") (pintype "passive"))
      (node (ref "C5") (pin "2") (pinfunction "2_2") (pintype "passive"))
      (node (ref "C6") (pin "2") (pinfunction "2_2") (pintype "passive"))
      (node (ref "C7") (pin "2") (pinfunction "2_2") (pintype "passive"))
      (node (ref "C8") (pin "2") (pinfunction "2_2") (pintype "passive"))
      (node (ref "C9") (pin "2") (pinfunction "2_2") (pintype "passive"))
      (node (ref "IC1") (pin "17") (pinfunction "GND_17") (pintype "power_in"))
      (node (ref "IC1") (pin "39") (pinfunction "GND_39") (pintype "power_in"))
      (node (ref "IC2") (pin "14") (pinfunction "GND_14") (pintype "power_in"))
      (node (ref "IC2") (pin "18") (pinfunction "GND_18") (pintype "power_in"))
      (node (ref "IC2") (pin "35") (pinfunction "GND_35") (pintype "power_in"))
      (node (ref "IC2") (pin "52") (pinfunction "GND_52") (pintype "power_in"))
      (node (ref "IC3") (pin "7") (pinfunction "GND_7") (pintype "power_in"))
      (node (ref "IC4") (pin "7") (pinfunction "GND_7") (pintype "power_in"))
      (node (ref "IC401") (pin "1") (pinfunction "I_1") (pintype "input"))
      (node (ref "IC401") (pin "3") (pinfunction "I_3") (pintype "input"))
      (node (ref "IC401") (pin "5") (pinfunction "I_5") (pintype "input"))
      (node (ref "IC401") (pin "7") (pinfunction "GND_7") (pintype "power_in"))
      (node (ref "IC402") (pin "12") (pinfunction "GND_12") (pintype "power_in"))
      (node (ref "IC5") (pin "12") (pinfunction "GND_12") (pintype "power_in"))
      (node (ref "IC5") (pin "34") (pinfunction "GND_34") (pintype "power_in"))
      (node (ref "J402") (pin "2") (pinfunction "2_2") (pintype "bidirectional"))
      (node (ref "LED1") (pin "K1") (pinfunction "K1_K1") (pintype "passive"))
      (node (ref "LED1") (pin "K2") (pinfunction "K2_K2") (pintype "passive"))
      (node (ref "LED1") (pin "K3") (pinfunction "K3_K3") (pintype "passive"))
      (node (ref "LED1") (pin "K4") (pinfunction "K4_K4") (pintype "passive"))
      (node (ref "LED2") (pin "K1") (pinfunction "K1_K1") (pintype "passive"))
      (node (ref "LED2") (pin "K2") (pinfunction "K2_K2") (pintype "passive"))
      (node (ref "LED2") (pin "K3") (pinfunction "K3_K3") (pintype "passive"))
      (node (ref "LED2") (pin "K4") (pinfunction "K4_K4") (pintype "passive"))
      (node (ref "LED3") (pin "K1") (pinfunction "K1_K1") (pintype "passive"))
      (node (ref "LED3") (pin "K2") (pinfunction "K2_K2") (pintype "passive"))
      (node (ref "LED3") (pin "K3") (pinfunction "K3_K3") (pintype "passive"))
      (node (ref "LED3") (pin "K4") (pinfunction "K4_K4") (pintype "passive"))
      (node (ref "LED4") (pin "K1") (pinfunction "K1_K1") (pintype "passive"))
      (node (ref "LED4") (pin "K2") (pinfunction "K2_K2") (pintype "passive"))
      (node (ref "LED4") (pin "K3") (pinfunction "K3_K3") (pintype "passive"))
      (node (ref "LED4") (pin "K4") (pinfunction "K4_K4") (pintype "passive"))
      (node (ref "OK401") (pin "5") (pinfunction "GND_5") (pintype "power_in"))
      (node (ref "QG101") (pin "4") (pinfunction "GND_4") (pintype "power_in"))
      (node (ref "R102") (pin "2") (pinfunction "2_2") (pintype "passive"))
      (node (ref "R103") (pin "2") (pinfunction "2_2") (pintype "passive"))
      (node (ref "SV101") (pin "17") (pinfunction "17_17") (pintype "passive"))
      (node (ref "SV101") (pin "18") (pinfunction "18_18") (pintype "passive"))
      (node (ref "SV101") (pin "3") (pinfunction "3_3") (pintype "passive"))
      (node (ref "SV101") (pin "4") (pinfunction "4_4") (pintype "passive"))
      (node (ref "SV101") (pin "45") (pinfunction "45_45") (pintype "passive"))
      (node (ref "SV101") (pin "46") (pinfunction "46_46") (pintype "passive"))
      (node (ref "SV101") (pin "63") (pinfunction "63_63") (pintype "passive"))
      (node (ref "SV101") (pin "64") (pinfunction "64_64") (pintype "passive"))
    )
    (net (code "41") (name "LED_APERTURE_BANK") (class "Default")
      (node (ref "IC3") (pin "8") (pinfunction "O_8") (pintype "output"))
      (node (ref "R3") (pin "2") (pinfunction "2_2") (pintype "passive"))
    )
    (net (code "42") (name "LED_BR") (class "Default")
      (node (ref "IC3") (pin "4") (pinfunction "O_4") (pintype "output"))
      (node (ref "R4") (pin "2") (pinfunction "2_2") (pintype "passive"))
    )
    (net (code "43") (name "LED_BUS_MBOX_IRQ") (class "Default")
      (node (ref "IC3") (pin "2") (pinfunction "O_2") (pintype "output"))
      (node (ref "R2") (pin "2") (pinfunction "2_2") (pintype "passive"))
    )
    (net (code "44") (name "LED_CPU_BG") (class "Default")
      (node (ref "IC4") (pin "6") (pinfunction "O_6") (pintype "output"))
      (node (ref "R7") (pin "2") (pinfunction "2_2") (pintype "passive"))
    )
    (net (code "45") (name "LED_CPU_HALT") (class "Default")
      (node (ref "IC3") (pin "12") (pinfunction "O_12") (pintype "output"))
      (node (ref "R6") (pin "2") (pinfunction "2_2") (pintype "passive"))
    )
    (net (code "46") (name "LED_CPU_MBOX_IRQ") (class "Default")
      (node (ref "IC4") (pin "4") (pinfunction "O_4") (pintype "output"))
      (node (ref "R8") (pin "2") (pinfunction "2_2") (pintype "passive"))
    )
    (net (code "47") (name "LED_CPU_RESET") (class "Default")
      (node (ref "IC3") (pin "10") (pinfunction "O_10") (pintype "output"))
      (node (ref "R5") (pin "2") (pinfunction "2_2") (pintype "passive"))
    )
    (net (code "48") (name "LED_MIDI_IRQ") (class "Default")
      (node (ref "IC4") (pin "2") (pinfunction "O_2") (pintype "output"))
      (node (ref "R10") (pin "2") (pinfunction "2_2") (pintype "passive"))
    )
    (net (code "49") (name "LED_MIDI_RX") (class "Default")
      (node (ref "IC4") (pin "10") (pinfunction "O_10") (pintype "output"))
      (node (ref "R11") (pin "2") (pinfunction "2_2") (pintype "passive"))
    )
    (net (code "50") (name "LED_MIDI_TX") (class "Default")
      (node (ref "IC4") (pin "12") (pinfunction "O_12") (pintype "output"))
      (node (ref "R12") (pin "2") (pinfunction "2_2") (pintype "passive"))
    )
    (net (code "51") (name "LED_STATUS_0") (class "Default")
      (node (ref "R13") (pin "2") (pinfunction "2_2") (pintype "passive"))
    )
    (net (code "52") (name "LED_STATUS_1") (class "Default")
      (node (ref "R14") (pin "2") (pinfunction "2_2") (pintype "passive"))
    )
    (net (code "53") (name "LED_STATUS_2") (class "Default")
      (node (ref "R15") (pin "2") (pinfunction "2_2") (pintype "passive"))
    )
    (net (code "54") (name "LED_STATUS_3") (class "Default")
      (node (ref "R16") (pin "2") (pinfunction "2_2") (pintype "passive"))
    )
    (net (code "55") (name "LED_YM3812_IRQ") (class "Default")
      (node (ref "IC4") (pin "8") (pinfunction "O_8") (pintype "output"))
      (node (ref "R9") (pin "2") (pinfunction "2_2") (pintype "passive"))
    )
    (net (code "56") (name "MIDI_RESET") (class "Default")
      (node (ref "IC401") (pin "8") (pinfunction "O_8") (pintype "output"))
      (node (ref "IC402") (pin "11") (pinfunction "RESET_11") (pintype "input"))
    )
    (net (code "57") (name "MIDI_RX") (class "Default")
      (node (ref "IC4") (pin "11") (pinfunction "I_11") (pintype "input"))
      (node (ref "IC402") (pin "2") (pinfunction "RXD_2") (pintype "input"))
      (node (ref "OK401") (pin "4") (pinfunction "OUT_4") (pintype "output"))
      (node (ref "R402") (pin "1") (pinfunction "1_1") (pintype "passive"))
    )
    (net (code "58") (name "MIDI_RX_+") (class "Default")
      (node (ref "D401") (pin "A") (pinfunction "A_A") (pintype "passive"))
      (node (ref "J401") (pin "5") (pinfunction "5_5") (pintype "bidirectional"))
      (node (ref "OK401") (pin "2") (pinfunction "C_2") (pintype "passive"))
    )
    (net (code "59") (name "MIDI_RX_-") (class "Default")
      (node (ref "D401") (pin "C") (pinfunction "C_C") (pintype "passive"))
      (node (ref "OK401") (pin "1") (pinfunction "A_1") (pintype "passive"))
      (node (ref "R401") (pin "2") (pinfunction "2_2") (pintype "passive"))
    )
    (net (code "60") (name "MIDI_TX") (class "Default")
      (node (ref "IC4") (pin "13") (pinfunction "I_13") (pintype "input"))
      (node (ref "IC401") (pin "13") (pinfunction "I_13") (pintype "input"))
      (node (ref "IC402") (pin "3") (pinfunction "TXD_3") (pintype "output"))
    )
    (net (code "61") (name "MIDI_TX_-") (class "Default")
      (node (ref "IC401") (pin "10") (pinfunction "O_10") (pintype "output"))
      (node (ref "J402") (pin "5") (pinfunction "5_5") (pintype "bidirectional"))
    )
    (net (code "62") (name "MIDI_UART_X1") (class "Default")
      (node (ref "C405") (pin "2") (pinfunction "2_2") (pintype "passive"))
      (node (ref "IC402") (pin "9") (pinfunction "X1/CLK_9") (pintype "passive"))
      (node (ref "Q401") (pin "1") (pinfunction "1_1") (pintype "passive"))
    )
    (net (code "63") (name "MIDI_UART_X2") (class "Default")
      (node (ref "C406") (pin "2") (pinfunction "2_2") (pintype "passive"))
      (node (ref "IC402") (pin "10") (pinfunction "X2_10") (pintype "passive"))
      (node (ref "Q401") (pin "2") (pinfunction "2_2") (pintype "passive"))
    )
    (net (code "64") (name "Net-(IC3C-O)") (class "Default")
      (node (ref "IC3") (pin "6") (pinfunction "O_6") (pintype "output"))
      (node (ref "IC3") (pin "9") (pinfunction "I_9") (pintype "input"))
    )
    (net (code "65") (name "Net-(IC401A-O)") (class "Default")
      (node (ref "IC401") (pin "11") (pinfunction "I_11") (pintype "input"))
      (node (ref "IC401") (pin "12") (pinfunction "O_12") (pintype "output"))
    )
    (net (code "66") (name "Net-(J401-Pad4)") (class "Default")
      (node (ref "J401") (pin "4") (pinfunction "4_4") (pintype "bidirectional"))
      (node (ref "R401") (pin "1") (pinfunction "1_1") (pintype "passive"))
    )
    (net (code "67") (name "Net-(J402-Pad4)") (class "Default")
      (node (ref "J402") (pin "4") (pinfunction "4_4") (pintype "bidirectional"))
      (node (ref "R406") (pin "1") (pinfunction "1_1") (pintype "passive"))
    )
    (net (code "68") (name "Net-(LED1-PadA1)") (class "Default")
      (node (ref "LED1") (pin "A1") (pinfunction "A1_A1") (pintype "passive"))
      (node (ref "R4") (pin "1") (pinfunction "1_1") (pintype "passive"))
    )
    (net (code "69") (name "Net-(LED1-PadA2)") (class "Default")
      (node (ref "LED1") (pin "A2") (pinfunction "A2_A2") (pintype "passive"))
      (node (ref "R3") (pin "1") (pinfunction "1_1") (pintype "passive"))
    )
    (net (code "70") (name "Net-(LED1-PadA3)") (class "Default")
      (node (ref "LED1") (pin "A3") (pinfunction "A3_A3") (pintype "passive"))
      (node (ref "R2") (pin "1") (pinfunction "1_1") (pintype "passive"))
    )
    (net (code "71") (name "Net-(LED1-PadA4)") (class "Default")
      (node (ref "LED1") (pin "A4") (pinfunction "A4_A4") (pintype "passive"))
      (node (ref "R1") (pin "1") (pinfunction "1_1") (pintype "passive"))
    )
    (net (code "72") (name "Net-(LED2-PadA1)") (class "Default")
      (node (ref "LED2") (pin "A1") (pinfunction "A1_A1") (pintype "passive"))
      (node (ref "R8") (pin "1") (pinfunction "1_1") (pintype "passive"))
    )
    (net (code "73") (name "Net-(LED2-PadA2)") (class "Default")
      (node (ref "LED2") (pin "A2") (pinfunction "A2_A2") (pintype "passive"))
      (node (ref "R7") (pin "1") (pinfunction "1_1") (pintype "passive"))
    )
    (net (code "74") (name "Net-(LED2-PadA3)") (class "Default")
      (node (ref "LED2") (pin "A3") (pinfunction "A3_A3") (pintype "passive"))
      (node (ref "R6") (pin "1") (pinfunction "1_1") (pintype "passive"))
    )
    (net (code "75") (name "Net-(LED2-PadA4)") (class "Default")
      (node (ref "LED2") (pin "A4") (pinfunction "A4_A4") (pintype "passive"))
      (node (ref "R5") (pin "1") (pinfunction "1_1") (pintype "passive"))
    )
    (net (code "76") (name "Net-(LED3-PadA1)") (class "Default")
      (node (ref "LED3") (pin "A1") (pinfunction "A1_A1") (pintype "passive"))
      (node (ref "R12") (pin "1") (pinfunction "1_1") (pintype "passive"))
    )
    (net (code "77") (name "Net-(LED3-PadA2)") (class "Default")
      (node (ref "LED3") (pin "A2") (pinfunction "A2_A2") (pintype "passive"))
      (node (ref "R11") (pin "1") (pinfunction "1_1") (pintype "passive"))
    )
    (net (code "78") (name "Net-(LED3-PadA3)") (class "Default")
      (node (ref "LED3") (pin "A3") (pinfunction "A3_A3") (pintype "passive"))
      (node (ref "R10") (pin "1") (pinfunction "1_1") (pintype "passive"))
    )
    (net (code "79") (name "Net-(LED3-PadA4)") (class "Default")
      (node (ref "LED3") (pin "A4") (pinfunction "A4_A4") (pintype "passive"))
      (node (ref "R9") (pin "1") (pinfunction "1_1") (pintype "passive"))
    )
    (net (code "80") (name "Net-(LED4-PadA1)") (class "Default")
      (node (ref "LED4") (pin "A1") (pinfunction "A1_A1") (pintype "passive"))
      (node (ref "R16") (pin "1") (pinfunction "1_1") (pintype "passive"))
    )
    (net (code "81") (name "Net-(LED4-PadA2)") (class "Default")
      (node (ref "LED4") (pin "A2") (pinfunction "A2_A2") (pintype "passive"))
      (node (ref "R15") (pin "1") (pinfunction "1_1") (pintype "passive"))
    )
    (net (code "82") (name "Net-(LED4-PadA3)") (class "Default")
      (node (ref "LED4") (pin "A3") (pinfunction "A3_A3") (pintype "passive"))
      (node (ref "R14") (pin "1") (pinfunction "1_1") (pintype "passive"))
    )
    (net (code "83") (name "Net-(LED4-PadA4)") (class "Default")
      (node (ref "LED4") (pin "A4") (pinfunction "A4_A4") (pintype "passive"))
      (node (ref "R13") (pin "1") (pinfunction "1_1") (pintype "passive"))
    )
    (net (code "84") (name "unconnected-(IC1-A19-Pad21)") (class "Default")
      (node (ref "IC1") (pin "21") (pinfunction "A19_21") (pintype "output"))
    )
    (net (code "85") (name "unconnected-(IC1-A20-Pad22)") (class "Default")
      (node (ref "IC1") (pin "22") (pinfunction "A20_22") (pintype "output"))
    )
    (net (code "86") (name "unconnected-(IC1-A21-Pad13)") (class "Default")
      (node (ref "IC1") (pin "13") (pinfunction "A21_13") (pintype "output"))
    )
    (net (code "87") (name "unconnected-(IC1-E-Pad42)") (class "Default")
      (node (ref "IC1") (pin "42") (pinfunction "E_42") (pintype "output"))
    )
    (net (code "88") (name "unconnected-(IC1-FC0-Pad50)") (class "Default")
      (node (ref "IC1") (pin "50") (pinfunction "FC0_50") (pintype "output"))
    )
    (net (code "89") (name "unconnected-(IC1-FC1-Pad49)") (class "Default")
      (node (ref "IC1") (pin "49") (pinfunction "FC1_49") (pintype "output"))
    )
    (net (code "90") (name "unconnected-(IC1-FC2-Pad48)") (class "Default")
      (node (ref "IC1") (pin "48") (pinfunction "FC2_48") (pintype "output"))
    )
    (net (code "91") (name "unconnected-(IC1-~{AS}-Pad31)") (class "Default")
      (node (ref "IC1") (pin "31") (pinfunction "~{AS}_31") (pintype "output"))
    )
    (net (code "92") (name "unconnected-(IC1-~{BERR}-Pad44)") (class "Default")
      (node (ref "IC1") (pin "44") (pinfunction "~{BERR}_44") (pintype "input"))
    )
    (net (code "93") (name "unconnected-(IC1-~{BGACK}-Pad36)") (class "Default")
      (node (ref "IC1") (pin "36") (pinfunction "~{BGACK}_36") (pintype "output"))
    )
    (net (code "94") (name "unconnected-(IC1-~{DS}-Pad32)") (class "Default")
      (node (ref "IC1") (pin "32") (pinfunction "~{DS}_32") (pintype "output"))
    )
    (net (code "95") (name "unconnected-(IC1-~{DTACK}-Pad34)") (class "Default")
      (node (ref "IC1") (pin "34") (pinfunction "~{DTACK}_34") (pintype "input"))
    )
    (net (code "96") (name "unconnected-(IC1-~{IPL0}-Pad47)") (class "Default")
      (node (ref "IC1") (pin "47") (pinfunction "~{IPL0}_47") (pintype "input"))
    )
    (net (code "97") (name "unconnected-(IC1-~{IPL1}-Pad45)") (class "Default")
      (node (ref "IC1") (pin "45") (pinfunction "~{IPL1}_45") (pintype "input"))
    )
    (net (code "98") (name "unconnected-(IC1-~{IPL2}-Pad46)") (class "Default")
      (node (ref "IC1") (pin "46") (pinfunction "~{IPL2}_46") (pintype "input"))
    )
    (net (code "99") (name "unconnected-(IC1-~{VPA}-Pad43)") (class "Default")
      (node (ref "IC1") (pin "43") (pinfunction "~{VPA}_43") (pintype "input"))
    )
    (net (code "100") (name "unconnected-(IC2-A0L-Pad55)") (class "Default")
      (node (ref "IC2") (pin "55") (pinfunction "A0L_55") (pintype "input"))
    )
    (net (code "101") (name "unconnected-(IC2-A0R-Pad48)") (class "Default")
      (node (ref "IC2") (pin "48") (pinfunction "A0R_48") (pintype "input"))
    )
    (net (code "102") (name "unconnected-(IC2-A1L-Pad56)") (class "Default")
      (node (ref "IC2") (pin "56") (pinfunction "A1L_56") (pintype "input"))
    )
    (net (code "103") (name "unconnected-(IC2-A1R-Pad47)") (class "Default")
      (node (ref "IC2") (pin "47") (pinfunction "A1R_47") (pintype "input"))
    )
    (net (code "104") (name "unconnected-(IC2-A2L-Pad57)") (class "Default")
      (node (ref "IC2") (pin "57") (pinfunction "A2L_57") (pintype "input"))
    )
    (net (code "105") (name "unconnected-(IC2-A2R-Pad46)") (class "Default")
      (node (ref "IC2") (pin "46") (pinfunction "A2R_46") (pintype "input"))
    )
    (net (code "106") (name "unconnected-(IC2-A3L-Pad58)") (class "Default")
      (node (ref "IC2") (pin "58") (pinfunction "A3L_58") (pintype "input"))
    )
    (net (code "107") (name "unconnected-(IC2-A3R-Pad45)") (class "Default")
      (node (ref "IC2") (pin "45") (pinfunction "A3R_45") (pintype "input"))
    )
    (net (code "108") (name "unconnected-(IC2-A4L-Pad59)") (class "Default")
      (node (ref "IC2") (pin "59") (pinfunction "A4L_59") (pintype "input"))
    )
    (net (code "109") (name "unconnected-(IC2-A4R-Pad44)") (class "Default")
      (node (ref "IC2") (pin "44") (pinfunction "A4R_44") (pintype "input"))
    )
    (net (code "110") (name "unconnected-(IC2-A5L-Pad60)") (class "Default")
      (node (ref "IC2") (pin "60") (pinfunction "A5L_60") (pintype "input"))
    )
    (net (code "111") (name "unconnected-(IC2-A5R-Pad43)") (class "Default")
      (node (ref "IC2") (pin "43") (pinfunction "A5R_43") (pintype "input"))
    )
    (net (code "112") (name "unconnected-(IC2-A6L-Pad61)") (class "Default")
      (node (ref "IC2") (pin "61") (pinfunction "A6L_61") (pintype "input"))
    )
    (net (code "113") (name "unconnected-(IC2-A6R-Pad42)") (class "Default")
      (node (ref "IC2") (pin "42") (pinfunction "A6R_42") (pintype "input"))
    )
    (net (code "114") (name "unconnected-(IC2-A7L-Pad62)") (class "Default")
      (node (ref "IC2") (pin "62") (pinfunction "A7L_62") (pintype "input"))
    )
    (net (code "115") (name "unconnected-(IC2-A7R-Pad41)") (class "Default")
      (node (ref "IC2") (pin "41") (pinfunction "A7R_41") (pintype "input"))
    )
    (net (code "116") (name "unconnected-(IC2-A8L-Pad63)") (class "Default")
      (node (ref "IC2") (pin "63") (pinfunction "A8L_63") (pintype "input"))
    )
    (net (code "117") (name "unconnected-(IC2-A8R-Pad40)") (class "Default")
      (node (ref "IC2") (pin "40") (pinfunction "A8R_40") (pintype "input"))
    )
    (net (code "118") (name "unconnected-(IC2-A9L-Pad64)") (class "Default")
      (node (ref "IC2") (pin "64") (pinfunction "A9L_64") (pintype "input"))
    )
    (net (code "119") (name "unconnected-(IC2-A9R-Pad39)") (class "Default")
      (node (ref "IC2") (pin "39") (pinfunction "A9R_39") (pintype "input"))
    )
    (net (code "120") (name "unconnected-(IC2-A10L-Pad65)") (class "Default")
      (node (ref "IC2") (pin "65") (pinfunction "A10L_65") (pintype "input"))
    )
    (net (code "121") (name "unconnected-(IC2-A10R-Pad38)") (class "Default")
      (node (ref "IC2") (pin "38") (pinfunction "A10R_38") (pintype "input"))
    )
    (net (code "122") (name "unconnected-(IC2-A11L-Pad66)") (class "Default")
      (node (ref "IC2") (pin "66") (pinfunction "A11L_66") (pintype "input"))
    )
    (net (code "123") (name "unconnected-(IC2-A11R-Pad37)") (class "Default")
      (node (ref "IC2") (pin "37") (pinfunction "A11R_37") (pintype "input"))
    )
    (net (code "124") (name "unconnected-(IC2-A12L-Pad67)") (class "Default")
      (node (ref "IC2") (pin "67") (pinfunction "A12L_67") (pintype "input"))
    )
    (net (code "125") (name "unconnected-(IC2-A12R-Pad36)") (class "Default")
      (node (ref "IC2") (pin "36") (pinfunction "A12R_36") (pintype "input"))
    )
    (net (code "126") (name "unconnected-(IC2-A13L-Pad1)") (class "Default")
      (node (ref "IC2") (pin "1") (pinfunction "A13L_1") (pintype "input"))
    )
    (net (code "127") (name "unconnected-(IC2-A13R-Pad34)") (class "Default")
      (node (ref "IC2") (pin "34") (pinfunction "A13R_34") (pintype "input"))
    )
    (net (code "128") (name "unconnected-(IC2-D0L-Pad8)") (class "Default")
      (node (ref "IC2") (pin "8") (pinfunction "D0L_8") (pintype "bidirectional"))
    )
    (net (code "129") (name "unconnected-(IC2-D0R-Pad19)") (class "Default")
      (node (ref "IC2") (pin "19") (pinfunction "D0R_19") (pintype "bidirectional"))
    )
    (net (code "130") (name "unconnected-(IC2-D1L-Pad9)") (class "Default")
      (node (ref "IC2") (pin "9") (pinfunction "D1L_9") (pintype "bidirectional"))
    )
    (net (code "131") (name "unconnected-(IC2-D1R-Pad20)") (class "Default")
      (node (ref "IC2") (pin "20") (pinfunction "D1R_20") (pintype "bidirectional"))
    )
    (net (code "132") (name "unconnected-(IC2-D2L-Pad10)") (class "Default")
      (node (ref "IC2") (pin "10") (pinfunction "D2L_10") (pintype "bidirectional"))
    )
    (net (code "133") (name "unconnected-(IC2-D2R-Pad21)") (class "Default")
      (node (ref "IC2") (pin "21") (pinfunction "D2R_21") (pintype "bidirectional"))
    )
    (net (code "134") (name "unconnected-(IC2-D3L-Pad11)") (class "Default")
      (node (ref "IC2") (pin "11") (pinfunction "D3L_11") (pintype "bidirectional"))
    )
    (net (code "135") (name "unconnected-(IC2-D3R-Pad23)") (class "Default")
      (node (ref "IC2") (pin "23") (pinfunction "D3R_23") (pintype "bidirectional"))
    )
    (net (code "136") (name "unconnected-(IC2-D4L-Pad12)") (class "Default")
      (node (ref "IC2") (pin "12") (pinfunction "D4L_12") (pintype "bidirectional"))
    )
    (net (code "137") (name "unconnected-(IC2-D4R-Pad24)") (class "Default")
      (node (ref "IC2") (pin "24") (pinfunction "D4R_24") (pintype "bidirectional"))
    )
    (net (code "138") (name "unconnected-(IC2-D5L-Pad13)") (class "Default")
      (node (ref "IC2") (pin "13") (pinfunction "D5L_13") (pintype "bidirectional"))
    )
    (net (code "139") (name "unconnected-(IC2-D5R-Pad25)") (class "Default")
      (node (ref "IC2") (pin "25") (pinfunction "D5R_25") (pintype "bidirectional"))
    )
    (net (code "140") (name "unconnected-(IC2-D6L-Pad15)") (class "Default")
      (node (ref "IC2") (pin "15") (pinfunction "D6L_15") (pintype "bidirectional"))
    )
    (net (code "141") (name "unconnected-(IC2-D6R-Pad26)") (class "Default")
      (node (ref "IC2") (pin "26") (pinfunction "D6R_26") (pintype "bidirectional"))
    )
    (net (code "142") (name "unconnected-(IC2-D7L-Pad16)") (class "Default")
      (node (ref "IC2") (pin "16") (pinfunction "D7L_16") (pintype "bidirectional"))
    )
    (net (code "143") (name "unconnected-(IC2-D7R-Pad27)") (class "Default")
      (node (ref "IC2") (pin "27") (pinfunction "D7R_27") (pintype "bidirectional"))
    )
    (net (code "144") (name "unconnected-(IC2-~{BUSY}L-Pad53)") (class "Default")
      (node (ref "IC2") (pin "53") (pinfunction "~{BUSY}L_53") (pintype "output"))
    )
    (net (code "145") (name "unconnected-(IC2-~{BUSY}R-Pad50)") (class "Default")
      (node (ref "IC2") (pin "50") (pinfunction "~{BUSY}R_50") (pintype "output"))
    )
    (net (code "146") (name "unconnected-(IC2-~{CE}L-Pad3)") (class "Default")
      (node (ref "IC2") (pin "3") (pinfunction "~{CE}L_3") (pintype "input"))
    )
    (net (code "147") (name "unconnected-(IC2-~{CE}R-Pad32)") (class "Default")
      (node (ref "IC2") (pin "32") (pinfunction "~{CE}R_32") (pintype "input"))
    )
    (net (code "148") (name "unconnected-(IC2-~{INT}L-Pad54)") (class "Default")
      (node (ref "IC2") (pin "54") (pinfunction "~{INT}L_54") (pintype "input"))
    )
    (net (code "149") (name "unconnected-(IC2-~{INT}R-Pad49)") (class "Default")
      (node (ref "IC2") (pin "49") (pinfunction "~{INT}R_49") (pintype "input"))
    )
    (net (code "150") (name "unconnected-(IC2-~{OE}L-Pad6)") (class "Default")
      (node (ref "IC2") (pin "6") (pinfunction "~{OE}L_6") (pintype "input"))
    )
    (net (code "151") (name "unconnected-(IC2-~{OE}R-Pad29)") (class "Default")
      (node (ref "IC2") (pin "29") (pinfunction "~{OE}R_29") (pintype "input"))
    )
    (net (code "152") (name "unconnected-(IC2-~{SEM}L-Pad4)") (class "Default")
      (node (ref "IC2") (pin "4") (pinfunction "~{SEM}L_4") (pintype "output"))
    )
    (net (code "153") (name "unconnected-(IC2-~{SEM}R-Pad31)") (class "Default")
      (node (ref "IC2") (pin "31") (pinfunction "~{SEM}R_31") (pintype "output"))
    )
    (net (code "154") (name "unconnected-(IC2-~{WE}L-Pad5)") (class "Default")
      (node (ref "IC2") (pin "5") (pinfunction "~{WE}L_5") (pintype "input"))
    )
    (net (code "155") (name "unconnected-(IC2-~{WE}R-Pad30)") (class "Default")
      (node (ref "IC2") (pin "30") (pinfunction "~{WE}R_30") (pintype "input"))
    )
    (net (code "156") (name "unconnected-(IC5-~{CS}-Pad8)") (class "Default")
      (node (ref "IC5") (pin "8") (pinfunction "~{CS}_8") (pintype "input"))
    )
    (net (code "157") (name "unconnected-(IC5-~{OE}-Pad37)") (class "Default")
      (node (ref "IC5") (pin "37") (pinfunction "~{OE}_37") (pintype "input"))
    )
    (net (code "158") (name "unconnected-(IC101A-A1-Pad2)") (class "Default")
      (node (ref "IC101") (pin "2") (pinfunction "A1_2") (pintype "bidirectional"))
    )
    (net (code "159") (name "unconnected-(IC101A-A2-Pad3)") (class "Default")
      (node (ref "IC101") (pin "3") (pinfunction "A2_3") (pintype "bidirectional"))
    )
    (net (code "160") (name "unconnected-(IC101A-A3-Pad4)") (class "Default")
      (node (ref "IC101") (pin "4") (pinfunction "A3_4") (pintype "bidirectional"))
    )
    (net (code "161") (name "unconnected-(IC101A-A4-Pad5)") (class "Default")
      (node (ref "IC101") (pin "5") (pinfunction "A4_5") (pintype "bidirectional"))
    )
    (net (code "162") (name "unconnected-(IC101A-A5-Pad6)") (class "Default")
      (node (ref "IC101") (pin "6") (pinfunction "A5_6") (pintype "bidirectional"))
    )
    (net (code "163") (name "unconnected-(IC101A-A6-Pad7)") (class "Default")
      (node (ref "IC101") (pin "7") (pinfunction "A6_7") (pintype "bidirectional"))
    )
    (net (code "164") (name "unconnected-(IC101A-A7-Pad8)") (class "Default")
      (node (ref "IC101") (pin "8") (pinfunction "A7_8") (pintype "bidirectional"))
    )
    (net (code "165") (name "unconnected-(IC101A-A8-Pad9)") (class "Default")
      (node (ref "IC101") (pin "9") (pinfunction "A8_9") (pintype "bidirectional"))
    )
    (net (code "166") (name "unconnected-(IC101A-B1-Pad18)") (class "Default")
      (node (ref "IC101") (pin "18") (pinfunction "B1_18") (pintype "bidirectional"))
    )
    (net (code "167") (name "unconnected-(IC101A-B2-Pad17)") (class "Default")
      (node (ref "IC101") (pin "17") (pinfunction "B2_17") (pintype "bidirectional"))
    )
    (net (code "168") (name "unconnected-(IC101A-B3-Pad16)") (class "Default")
      (node (ref "IC101") (pin "16") (pinfunction "B3_16") (pintype "bidirectional"))
    )
    (net (code "169") (name "unconnected-(IC101A-B4-Pad15)") (class "Default")
      (node (ref "IC101") (pin "15") (pinfunction "B4_15") (pintype "bidirectional"))
    )
    (net (code "170") (name "unconnected-(IC101A-B5-Pad14)") (class "Default")
      (node (ref "IC101") (pin "14") (pinfunction "B5_14") (pintype "bidirectional"))
    )
    (net (code "171") (name "unconnected-(IC101A-B6-Pad13)") (class "Default")
      (node (ref "IC101") (pin "13") (pinfunction "B6_13") (pintype "bidirectional"))
    )
    (net (code "172") (name "unconnected-(IC101A-B7-Pad12)") (class "Default")
      (node (ref "IC101") (pin "12") (pinfunction "B7_12") (pintype "bidirectional"))
    )
    (net (code "173") (name "unconnected-(IC101A-B8-Pad11)") (class "Default")
      (node (ref "IC101") (pin "11") (pinfunction "B8_11") (pintype "bidirectional"))
    )
    (net (code "174") (name "unconnected-(IC101A-DIR-Pad1)") (class "Default")
      (node (ref "IC101") (pin "1") (pinfunction "DIR_1") (pintype "input"))
    )
    (net (code "175") (name "unconnected-(IC101A-G-Pad19)") (class "Default")
      (node (ref "IC101") (pin "19") (pinfunction "G_19") (pintype "input"))
    )
    (net (code "176") (name "unconnected-(IC401D-O-Pad2)") (class "Default")
      (node (ref "IC401") (pin "2") (pinfunction "O_2") (pintype "output"))
    )
    (net (code "177") (name "unconnected-(IC401E-O-Pad4)") (class "Default")
      (node (ref "IC401") (pin "4") (pinfunction "O_4") (pintype "output"))
    )
    (net (code "178") (name "unconnected-(IC401F-O-Pad6)") (class "Default")
      (node (ref "IC401") (pin "6") (pinfunction "O_6") (pintype "output"))
    )
    (net (code "179") (name "unconnected-(IC402-MPI-Pad5)") (class "Default")
      (node (ref "IC402") (pin "5") (pinfunction "MPI_5") (pintype "input"))
    )
    (net (code "180") (name "unconnected-(IC402-MPO-Pad4)") (class "Default")
      (node (ref "IC402") (pin "4") (pinfunction "MPO_4") (pintype "output"))
    )
    (net (code "181") (name "unconnected-(J401-Pad1)") (class "Default")
      (node (ref "J401") (pin "1") (pinfunction "1_1") (pintype "bidirectional"))
    )
    (net (code "182") (name "unconnected-(J401-Pad2)") (class "Default")
      (node (ref "J401") (pin "2") (pinfunction "2_2") (pintype "bidirectional"))
    )
    (net (code "183") (name "unconnected-(J401-Pad3)") (class "Default")
      (node (ref "J401") (pin "3") (pinfunction "3_3") (pintype "bidirectional"))
    )
    (net (code "184") (name "unconnected-(J402-Pad1)") (class "Default")
      (node (ref "J402") (pin "1") (pinfunction "1_1") (pintype "bidirectional"))
    )
    (net (code "185") (name "unconnected-(J402-Pad3)") (class "Default")
      (node (ref "J402") (pin "3") (pinfunction "3_3") (pintype "bidirectional"))
    )
    (net (code "186") (name "unconnected-(QG101-TS-Pad1)") (class "Default")
      (node (ref "QG101") (pin "1") (pinfunction "TS_1") (pintype "passive"))
    )
    (net (code "187") (name "unconnected-(SV101-Pad5)") (class "Default")
      (node (ref "SV101") (pin "5") (pinfunction "5_5") (pintype "passive"))
    )
    (net (code "188") (name "unconnected-(SV101-Pad6)") (class "Default")
      (node (ref "SV101") (pin "6") (pinfunction "6_6") (pintype "passive"))
    )
    (net (code "189") (name "unconnected-(SV101-Pad7)") (class "Default")
      (node (ref "SV101") (pin "7") (pinfunction "7_7") (pintype "passive"))
    )
    (net (code "190") (name "unconnected-(SV101-Pad8)") (class "Default")
      (node (ref "SV101") (pin "8") (pinfunction "8_8") (pintype "passive"))
    )
    (net (code "191") (name "unconnected-(SV101-Pad9)") (class "Default")
      (node (ref "SV101") (pin "9") (pinfunction "9_9") (pintype "passive"))
    )
    (net (code "192") (name "unconnected-(SV101-Pad10)") (class "Default")
      (node (ref "SV101") (pin "10") (pinfunction "10_10") (pintype "passive"))
    )
    (net (code "193") (name "unconnected-(SV101-Pad11)") (class "Default")
      (node (ref "SV101") (pin "11") (pinfunction "11_11") (pintype "passive"))
    )
    (net (code "194") (name "unconnected-(SV101-Pad12)") (class "Default")
      (node (ref "SV101") (pin "12") (pinfunction "12_12") (pintype "passive"))
    )
    (net (code "195") (name "unconnected-(SV101-Pad13)") (class "Default")
      (node (ref "SV101") (pin "13") (pinfunction "13_13") (pintype "passive"))
    )
    (net (code "196") (name "unconnected-(SV101-Pad14)") (class "Default")
      (node (ref "SV101") (pin "14") (pinfunction "14_14") (pintype "passive"))
    )
    (net (code "197") (name "unconnected-(SV101-Pad15)") (class "Default")
      (node (ref "SV101") (pin "15") (pinfunction "15_15") (pintype "passive"))
    )
    (net (code "198") (name "unconnected-(SV101-Pad16)") (class "Default")
      (node (ref "SV101") (pin "16") (pinfunction "16_16") (pintype "passive"))
    )
    (net (code "199") (name "unconnected-(SV101-Pad19)") (class "Default")
      (node (ref "SV101") (pin "19") (pinfunction "19_19") (pintype "passive"))
    )
    (net (code "200") (name "unconnected-(SV101-Pad20)") (class "Default")
      (node (ref "SV101") (pin "20") (pinfunction "20_20") (pintype "passive"))
    )
    (net (code "201") (name "unconnected-(SV101-Pad21)") (class "Default")
      (node (ref "SV101") (pin "21") (pinfunction "21_21") (pintype "passive"))
    )
    (net (code "202") (name "unconnected-(SV101-Pad22)") (class "Default")
      (node (ref "SV101") (pin "22") (pinfunction "22_22") (pintype "passive"))
    )
    (net (code "203") (name "unconnected-(SV101-Pad23)") (class "Default")
      (node (ref "SV101") (pin "23") (pinfunction "23_23") (pintype "passive"))
    )
    (net (code "204") (name "unconnected-(SV101-Pad24)") (class "Default")
      (node (ref "SV101") (pin "24") (pinfunction "24_24") (pintype "passive"))
    )
    (net (code "205") (name "unconnected-(SV101-Pad25)") (class "Default")
      (node (ref "SV101") (pin "25") (pinfunction "25_25") (pintype "passive"))
    )
    (net (code "206") (name "unconnected-(SV101-Pad26)") (class "Default")
      (node (ref "SV101") (pin "26") (pinfunction "26_26") (pintype "passive"))
    )
    (net (code "207") (name "unconnected-(SV101-Pad27)") (class "Default")
      (node (ref "SV101") (pin "27") (pinfunction "27_27") (pintype "passive"))
    )
    (net (code "208") (name "unconnected-(SV101-Pad28)") (class "Default")
      (node (ref "SV101") (pin "28") (pinfunction "28_28") (pintype "passive"))
    )
    (net (code "209") (name "unconnected-(SV101-Pad29)") (class "Default")
      (node (ref "SV101") (pin "29") (pinfunction "29_29") (pintype "passive"))
    )
    (net (code "210") (name "unconnected-(SV101-Pad30)") (class "Default")
      (node (ref "SV101") (pin "30") (pinfunction "30_30") (pintype "passive"))
    )
    (net (code "211") (name "unconnected-(SV101-Pad31)") (class "Default")
      (node (ref "SV101") (pin "31") (pinfunction "31_31") (pintype "passive"))
    )
    (net (code "212") (name "unconnected-(SV101-Pad32)") (class "Default")
      (node (ref "SV101") (pin "32") (pinfunction "32_32") (pintype "passive"))
    )
    (net (code "213") (name "unconnected-(SV101-Pad33)") (class "Default")
      (node (ref "SV101") (pin "33") (pinfunction "33_33") (pintype "passive"))
    )
    (net (code "214") (name "unconnected-(SV101-Pad34)") (class "Default")
      (node (ref "SV101") (pin "34") (pinfunction "34_34") (pintype "passive"))
    )
    (net (code "215") (name "unconnected-(SV101-Pad35)") (class "Default")
      (node (ref "SV101") (pin "35") (pinfunction "35_35") (pintype "passive"))
    )
    (net (code "216") (name "unconnected-(SV101-Pad36)") (class "Default")
      (node (ref "SV101") (pin "36") (pinfunction "36_36") (pintype "passive"))
    )
    (net (code "217") (name "unconnected-(SV101-Pad37)") (class "Default")
      (node (ref "SV101") (pin "37") (pinfunction "37_37") (pintype "passive"))
    )
    (net (code "218") (name "unconnected-(SV101-Pad38)") (class "Default")
      (node (ref "SV101") (pin "38") (pinfunction "38_38") (pintype "passive"))
    )
    (net (code "219") (name "unconnected-(SV101-Pad39)") (class "Default")
      (node (ref "SV101") (pin "39") (pinfunction "39_39") (pintype "passive"))
    )
    (net (code "220") (name "unconnected-(SV101-Pad40)") (class "Default")
      (node (ref "SV101") (pin "40") (pinfunction "40_40") (pintype "passive"))
    )
    (net (code "221") (name "unconnected-(SV101-Pad41)") (class "Default")
      (node (ref "SV101") (pin "41") (pinfunction "41_41") (pintype "passive"))
    )
    (net (code "222") (name "unconnected-(SV101-Pad42)") (class "Default")
      (node (ref "SV101") (pin "42") (pinfunction "42_42") (pintype "passive"))
    )
    (net (code "223") (name "unconnected-(SV101-Pad43)") (class "Default")
      (node (ref "SV101") (pin "43") (pinfunction "43_43") (pintype "passive"))
    )
    (net (code "224") (name "unconnected-(SV101-Pad44)") (class "Default")
      (node (ref "SV101") (pin "44") (pinfunction "44_44") (pintype "passive"))
    )
    (net (code "225") (name "unconnected-(SV101-Pad47)") (class "Default")
      (node (ref "SV101") (pin "47") (pinfunction "47_47") (pintype "passive"))
    )
    (net (code "226") (name "unconnected-(SV101-Pad48)") (class "Default")
      (node (ref "SV101") (pin "48") (pinfunction "48_48") (pintype "passive"))
    )
    (net (code "227") (name "unconnected-(SV101-Pad49)") (class "Default")
      (node (ref "SV101") (pin "49") (pinfunction "49_49") (pintype "passive"))
    )
    (net (code "228") (name "unconnected-(SV101-Pad50)") (class "Default")
      (node (ref "SV101") (pin "50") (pinfunction "50_50") (pintype "passive"))
    )
    (net (code "229") (name "unconnected-(SV101-Pad51)") (class "Default")
      (node (ref "SV101") (pin "51") (pinfunction "51_51") (pintype "passive"))
    )
    (net (code "230") (name "unconnected-(SV101-Pad52)") (class "Default")
      (node (ref "SV101") (pin "52") (pinfunction "52_52") (pintype "passive"))
    )
    (net (code "231") (name "unconnected-(SV101-Pad53)") (class "Default")
      (node (ref "SV101") (pin "53") (pinfunction "53_53") (pintype "passive"))
    )
    (net (code "232") (name "unconnected-(SV101-Pad54)") (class "Default")
      (node (ref "SV101") (pin "54") (pinfunction "54_54") (pintype "passive"))
    )
    (net (code "233") (name "unconnected-(SV101-Pad55)") (class "Default")
      (node (ref "SV101") (pin "55") (pinfunction "55_55") (pintype "passive"))
    )
    (net (code "234") (name "unconnected-(SV101-Pad56)") (class "Default")
      (node (ref "SV101") (pin "56") (pinfunction "56_56") (pintype "passive"))
    )
    (net (code "235") (name "unconnected-(SV101-Pad57)") (class "Default")
      (node (ref "SV101") (pin "57") (pinfunction "57_57") (pintype "passive"))
    )
    (net (code "236") (name "unconnected-(SV101-Pad58)") (class "Default")
      (node (ref "SV101") (pin "58") (pinfunction "58_58") (pintype "passive"))
    )
    (net (code "237") (name "unconnected-(SV101-Pad59)") (class "Default")
      (node (ref "SV101") (pin "59") (pinfunction "59_59") (pintype "passive"))
    )
    (net (code "238") (name "unconnected-(SV101-Pad60)") (class "Default")
      (node (ref "SV101") (pin "60") (pinfunction "60_60") (pintype "passive"))
    )
    (net (code "239") (name "unconnected-(SV101-Pad61)") (class "Default")
      (node (ref "SV101") (pin "61") (pinfunction "61_61") (pintype "passive"))
    )
    (net (code "240") (name "unconnected-(SV101-Pad62)") (class "Default")
      (node (ref "SV101") (pin "62") (pinfunction "62_62") (pintype "passive"))
    )
    (net (code "241") (name "~{BUS_MBOX_IRQ}") (class "Default")
      (node (ref "IC3") (pin "1") (pinfunction "I_1") (pintype "input"))
    )
    (net (code "242") (name "~{CPU_BG}") (class "Default")
      (node (ref "IC1") (pin "35") (pinfunction "~{BG}_35") (pintype "output"))
      (node (ref "IC4") (pin "5") (pinfunction "I_5") (pintype "input"))
    )
    (net (code "243") (name "~{CPU_BR}") (class "Default")
      (node (ref "IC1") (pin "37") (pinfunction "~{BR}_37") (pintype "input"))
      (node (ref "IC3") (pin "3") (pinfunction "I_3") (pintype "input"))
    )
    (net (code "244") (name "~{CPU_HALT}") (class "Default")
      (node (ref "IC1") (pin "40") (pinfunction "~{HALT}_40") (pintype "bidirectional"))
      (node (ref "IC3") (pin "13") (pinfunction "I_13") (pintype "input"))
    )
    (net (code "245") (name "~{CPU_MBOX_IRQ}") (class "Default")
      (node (ref "IC4") (pin "3") (pinfunction "I_3") (pintype "input"))
    )
    (net (code "246") (name "~{CPU_RESET}") (class "Default")
      (node (ref "IC1") (pin "41") (pinfunction "~{RESET}_41") (pintype "bidirectional"))
      (node (ref "IC3") (pin "11") (pinfunction "I_11") (pintype "input"))
      (node (ref "IC401") (pin "9") (pinfunction "I_9") (pintype "input"))
    )
    (net (code "247") (name "~{MIDI_IRQ}") (class "Default")
      (node (ref "IC4") (pin "1") (pinfunction "I_1") (pintype "input"))
      (node (ref "IC402") (pin "13") (pinfunction "~{IRQ}_13") (pintype "output"))
      (node (ref "R407") (pin "1") (pinfunction "1_1") (pintype "passive"))
    )
    (net (code "248") (name "~{MIDI_UART_CS}") (class "Default")
      (node (ref "IC402") (pin "14") (pinfunction "~{CS}_14") (pintype "input"))
    )
    (net (code "249") (name "~{RD}") (class "Default")
      (node (ref "IC402") (pin "1") (pinfunction "~{RD}_1") (pintype "input"))
    )
    (net (code "250") (name "~{YM3812_IRQ}") (class "Default")
      (node (ref "IC4") (pin "9") (pinfunction "I_9") (pintype "input"))
    )
  )
)
